# EEG_cap_v1.net
KiCad netlist of a schematic drawn in EAGLE
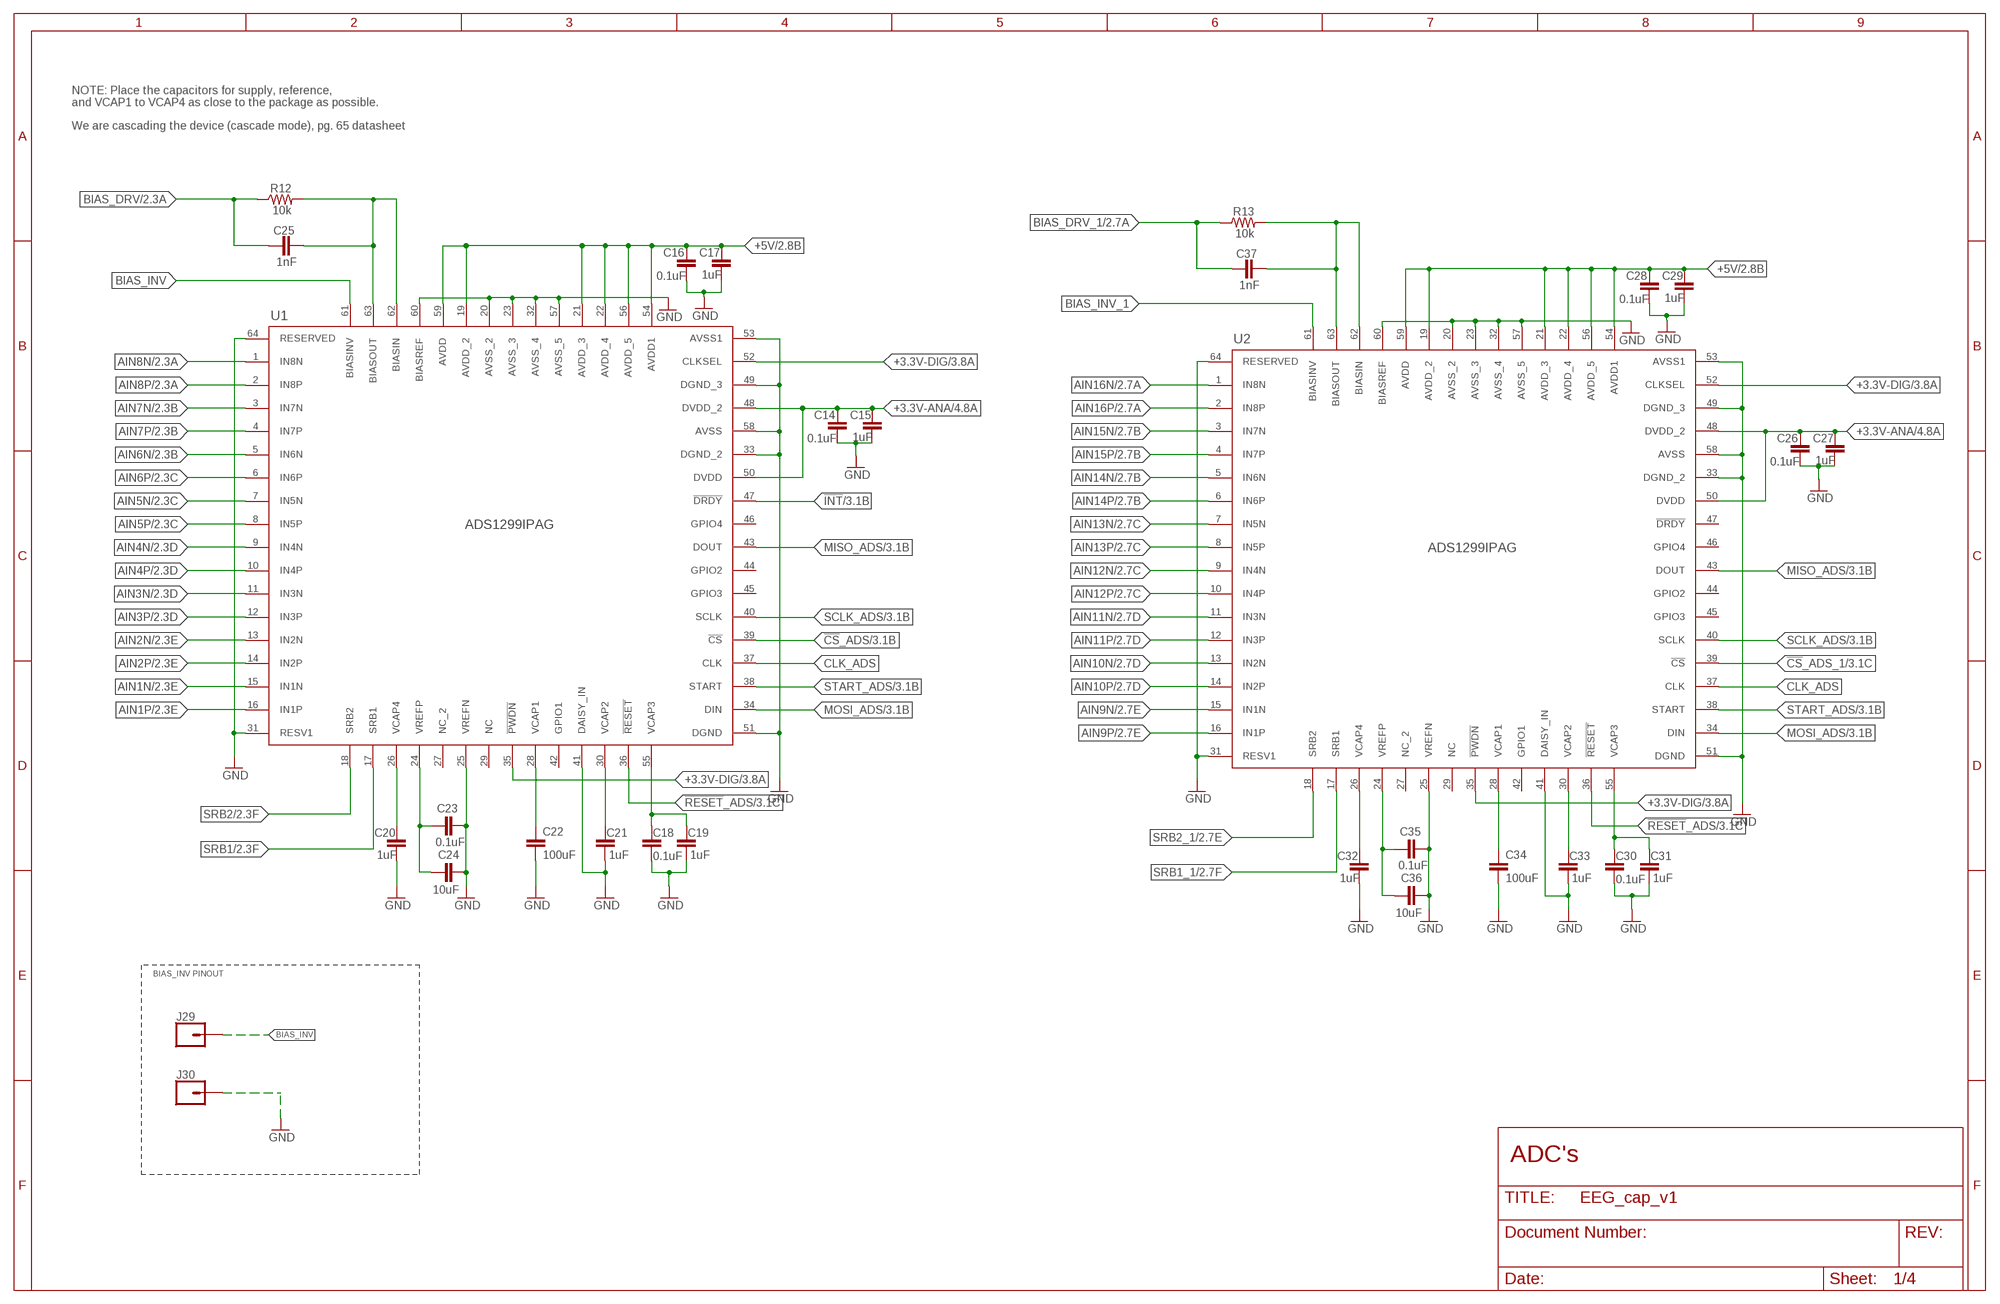
[diagram p0: schematic, sheet 1]
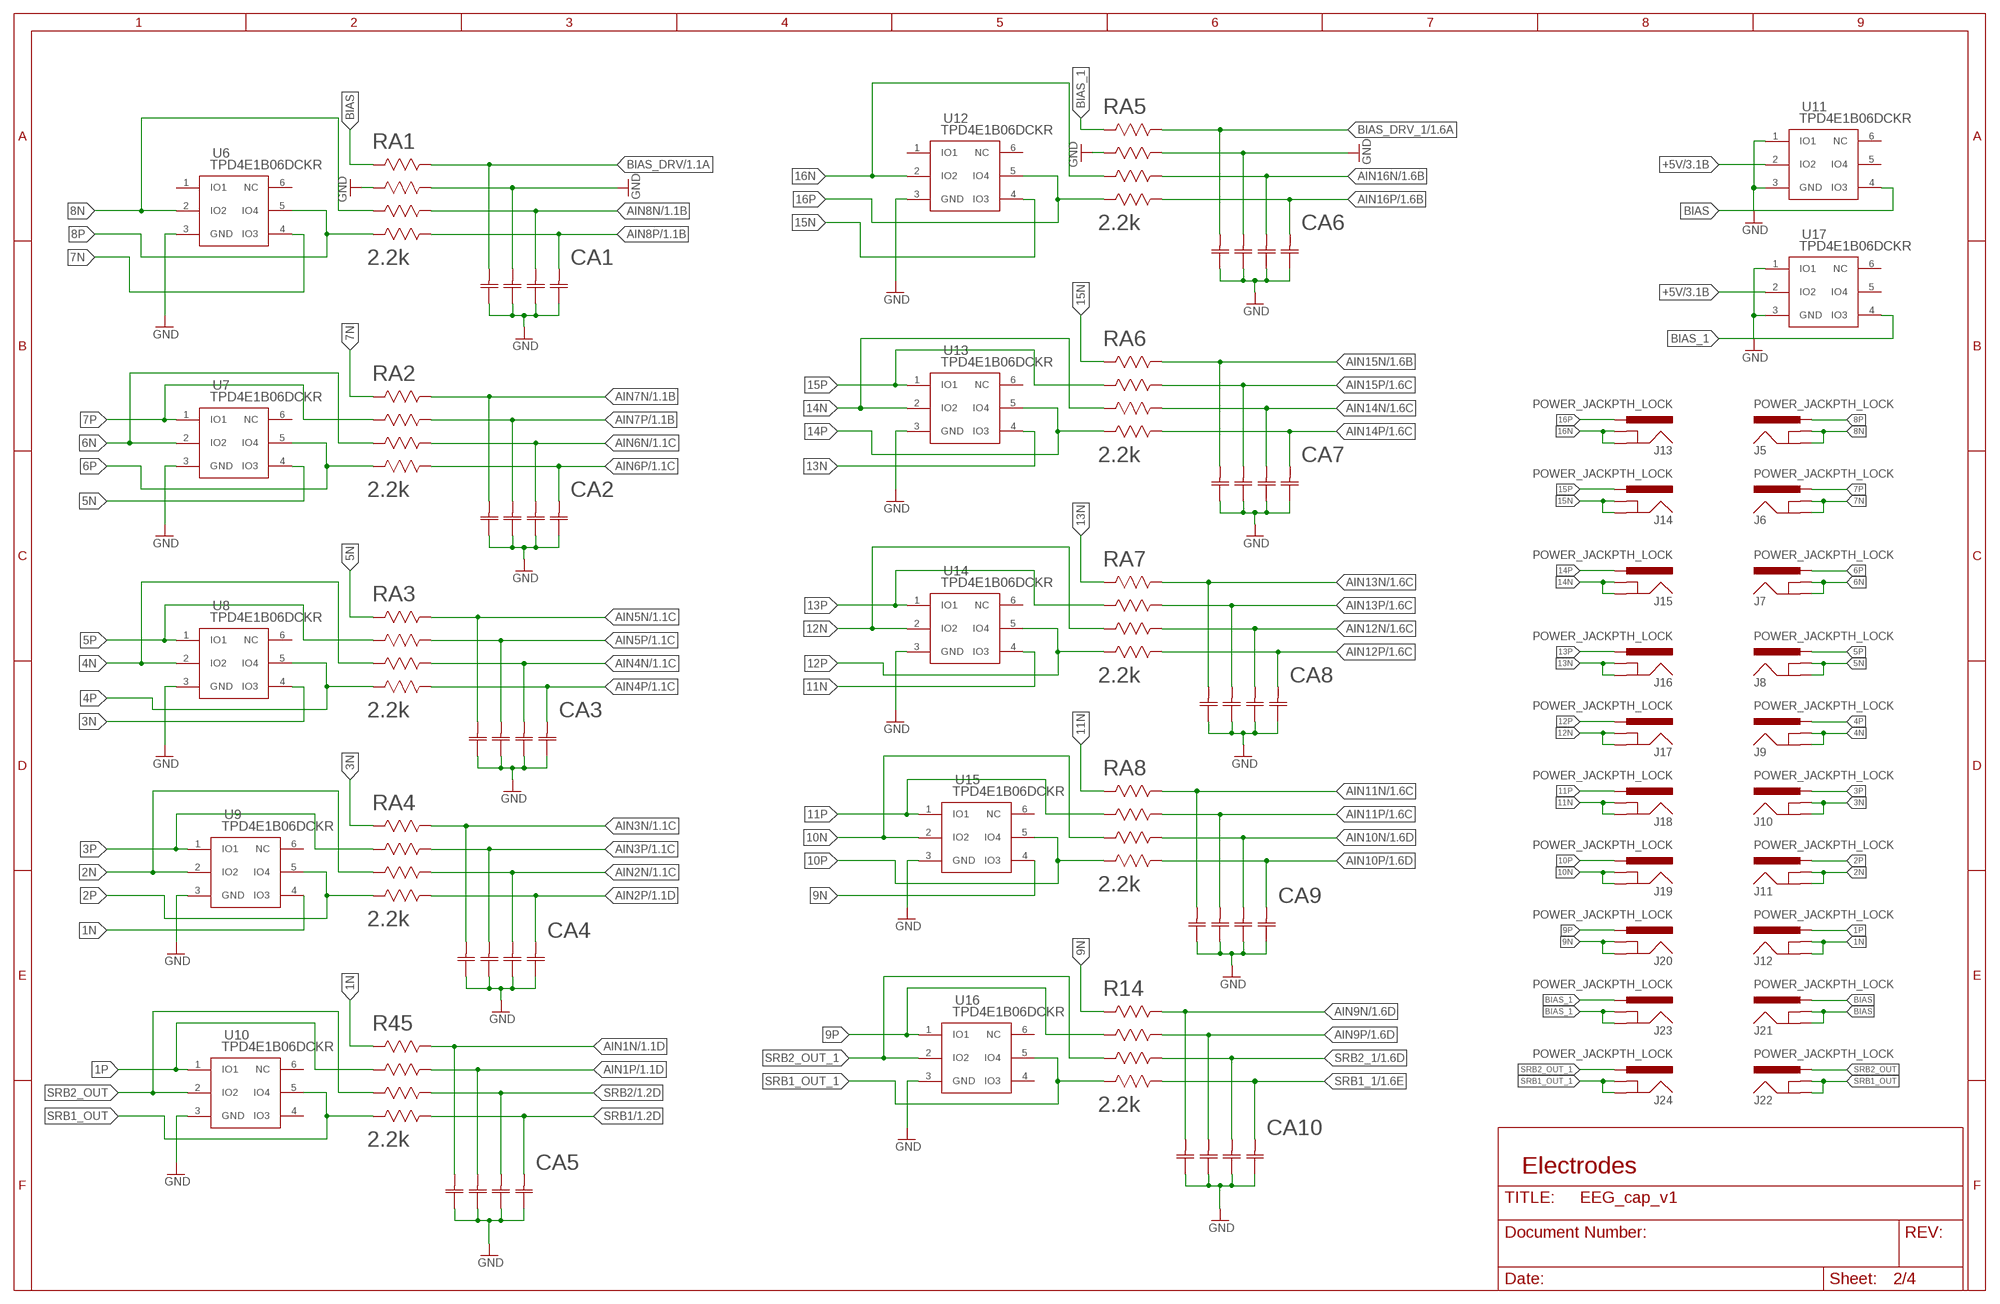
[diagram p1: schematic, sheet 2]
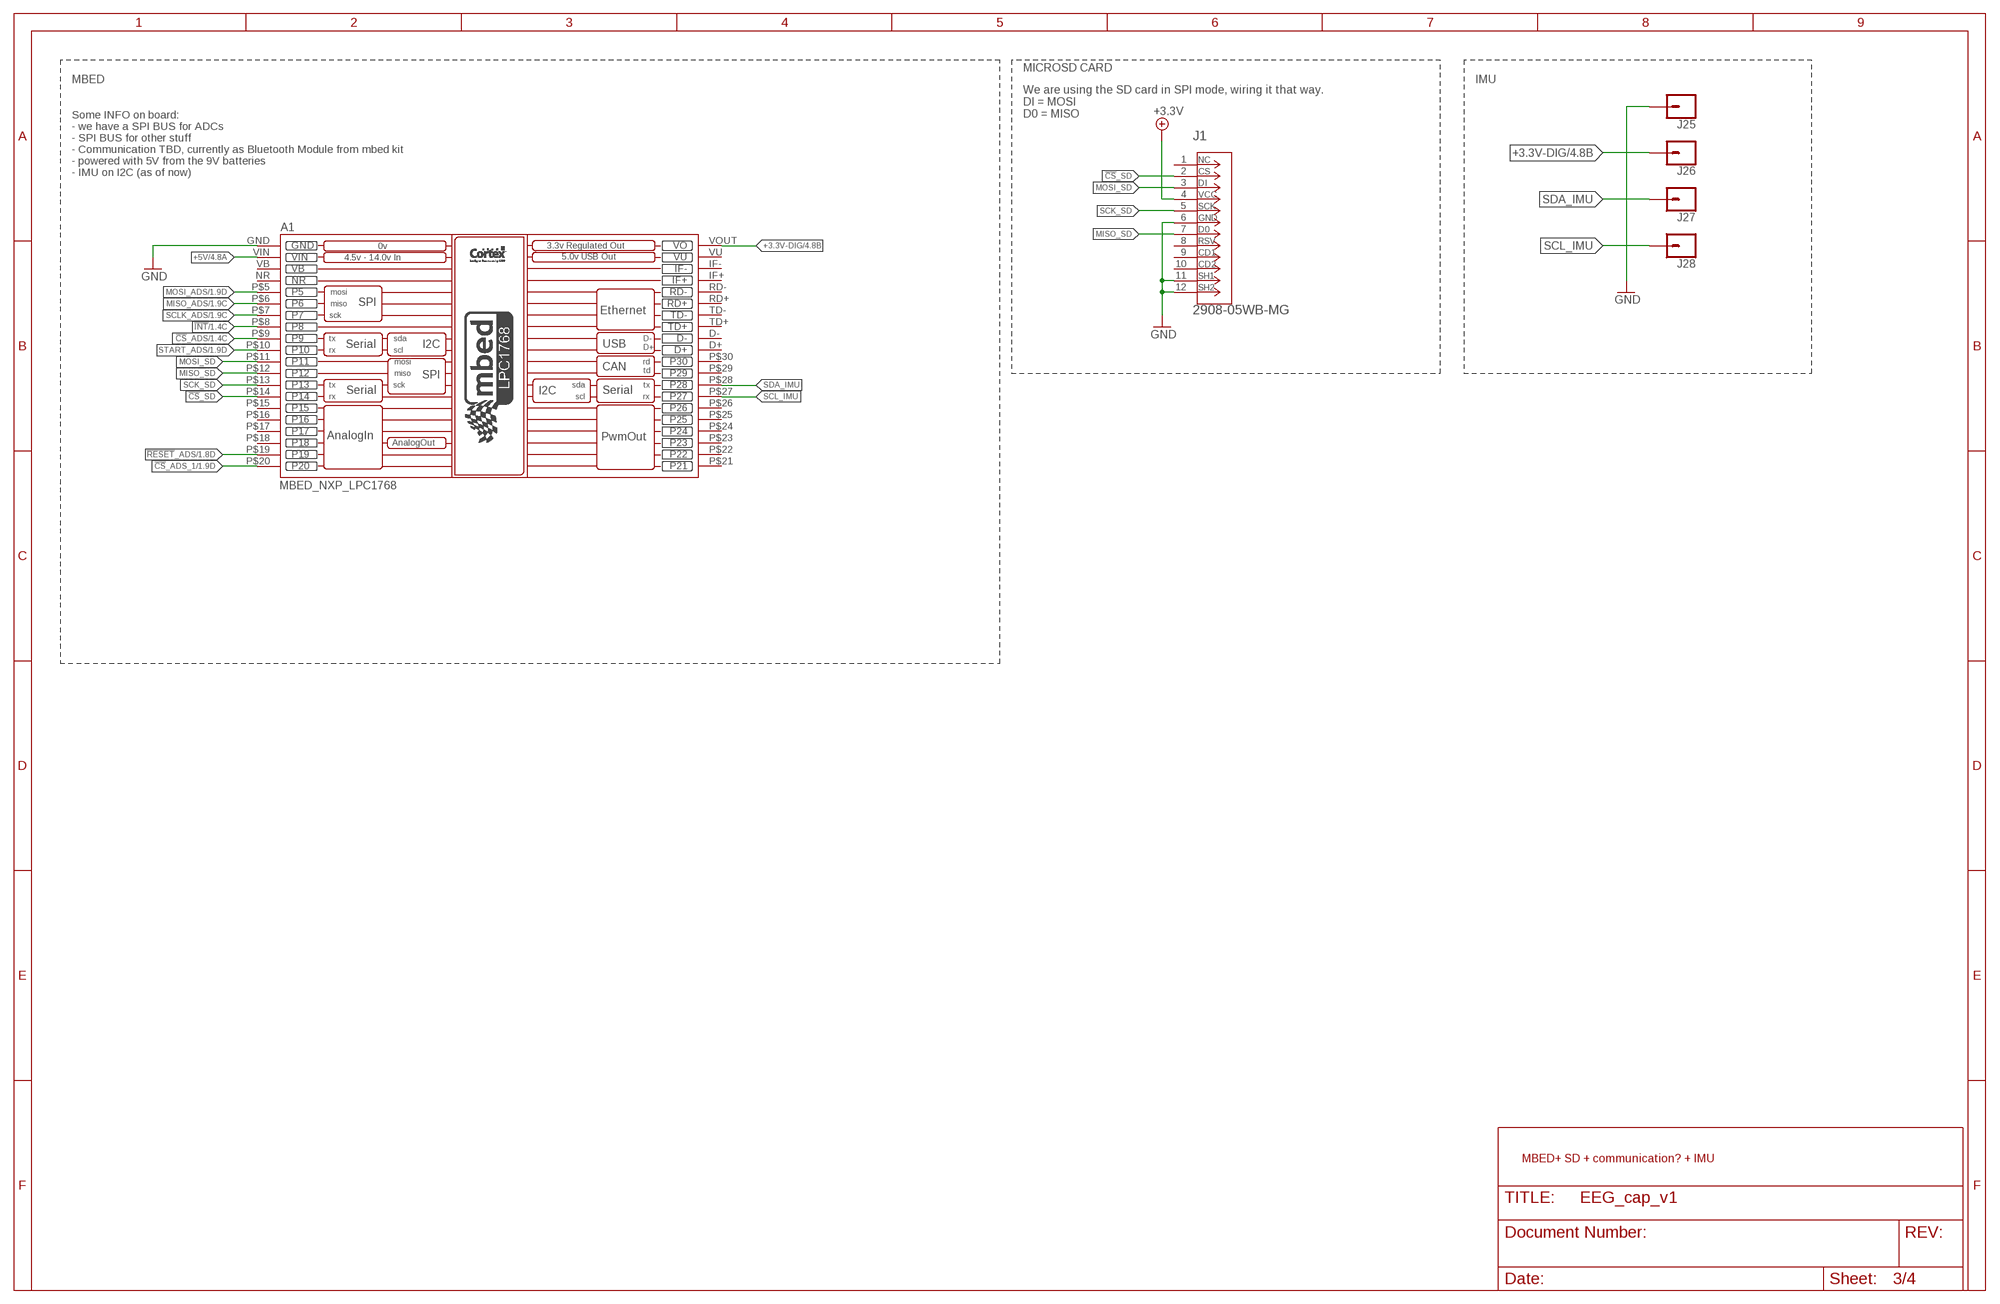
[diagram p2: schematic, sheet 3]
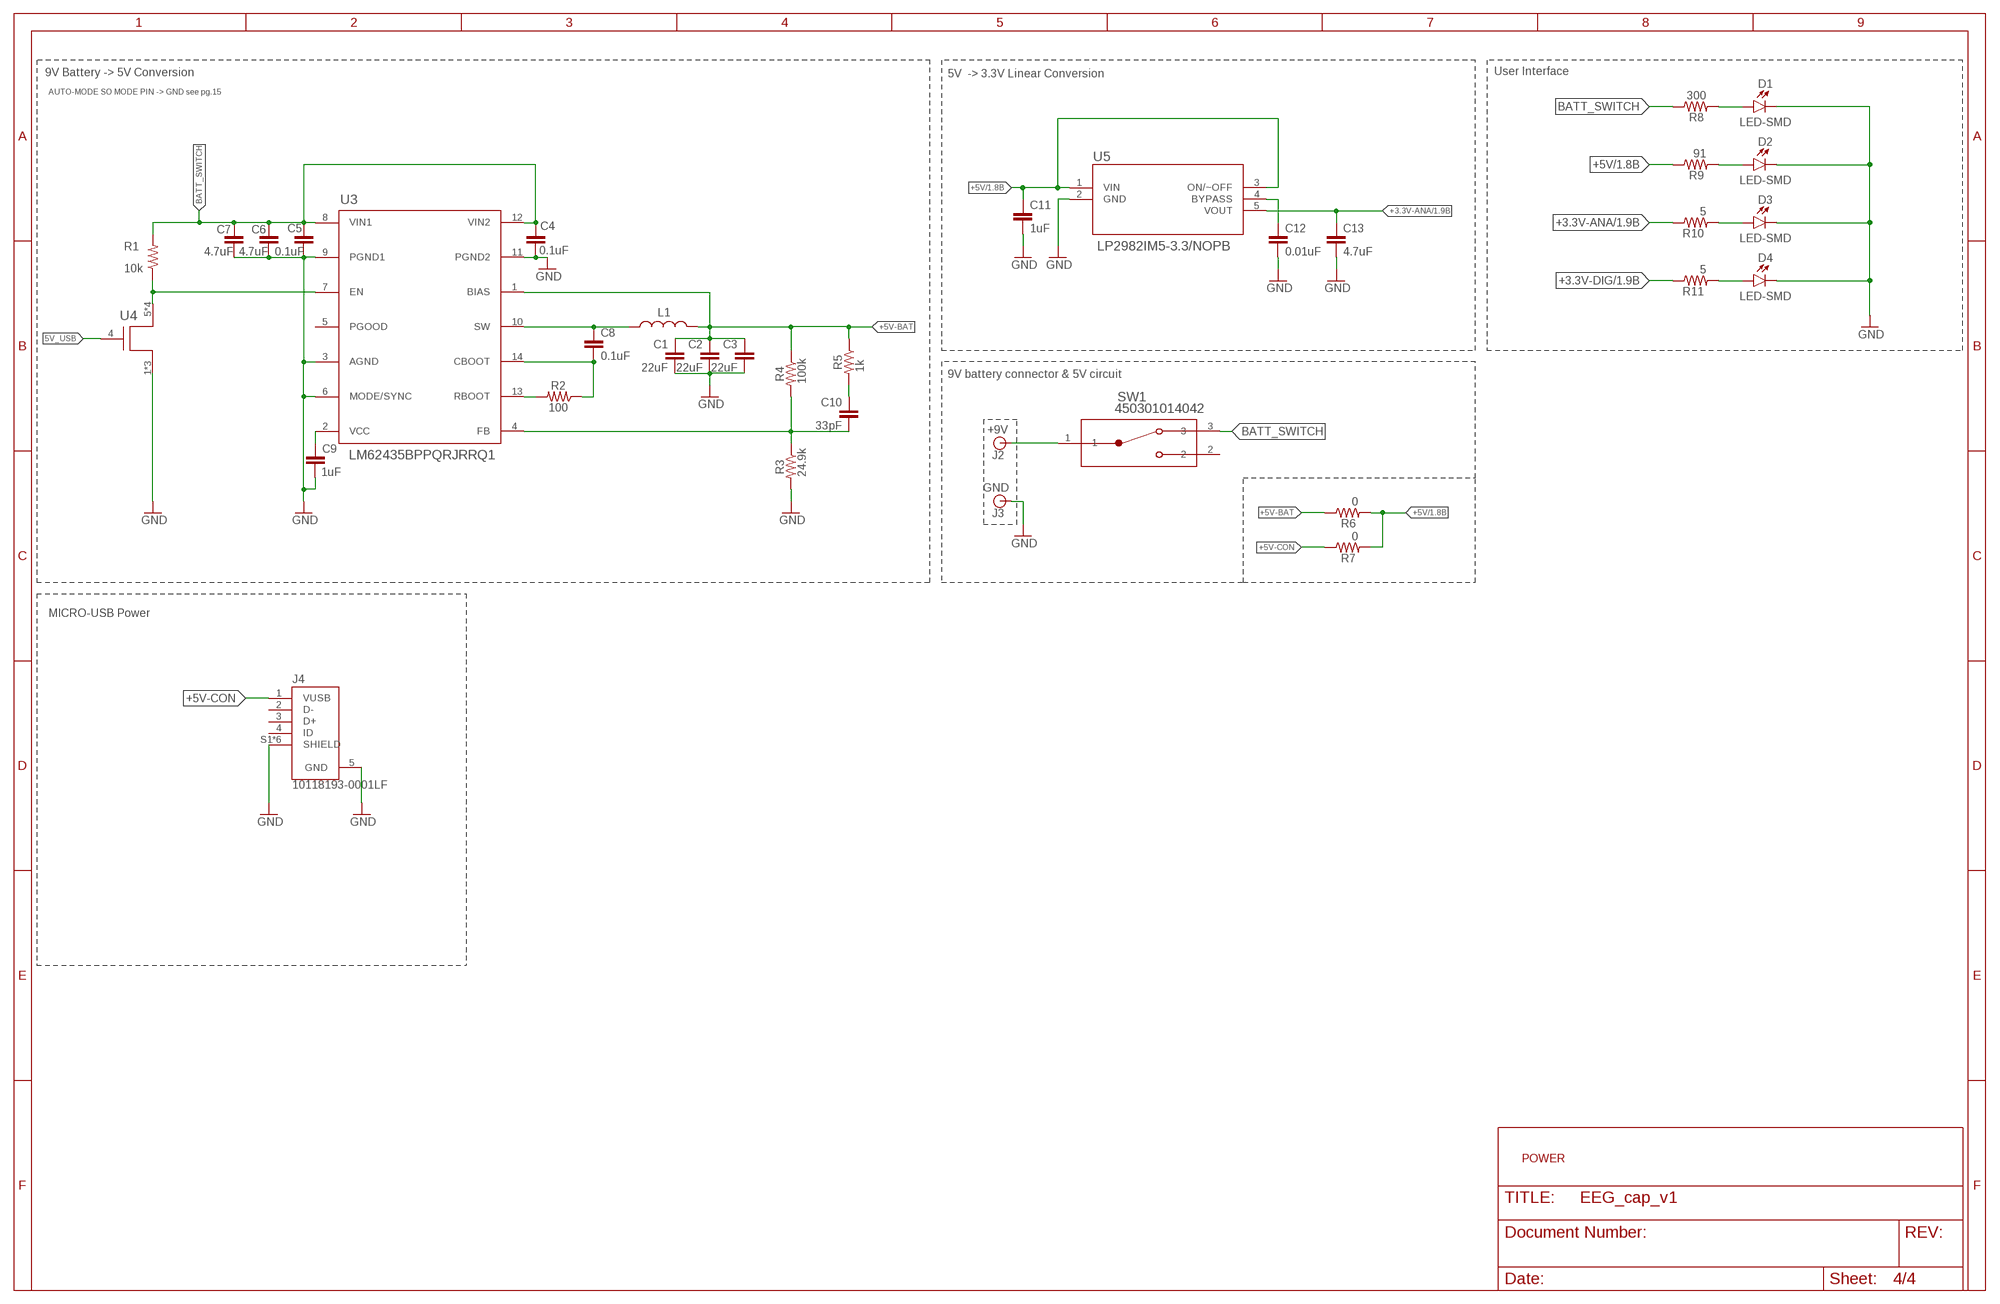
[diagram p3: schematic, sheet 4]

(export (version "E")
  (design (tool "Eeschema 10.0.6"))
  (components
    (comp (ref "A1")
      (value "MBED_NXP_LPC1768")
      (footprint "eagle-import:MBED_LPC1768")
      (libsource (lib "eagle-import") (part "MBED_NXP_LPC1768"))
    )
    (comp (ref "J1")
      (value "2908-05WB-MG")
      (footprint "eagle-import:CONN_3M_2900")
      (fields (field (name "COPYRIGHT") "Copyright (C) 2021 Ultra Librarian. All rights reserved."))
      (libsource (lib "eagle-import") (part "2908-05WB-MG"))
    )
    (comp (ref "J25")
      (value "CONN_01")
      (footprint "eagle-import:1X01")
      (libsource (lib "eagle-import") (part "CONN_01"))
    )
    (comp (ref "J26")
      (value "CONN_01")
      (footprint "eagle-import:1X01")
      (libsource (lib "eagle-import") (part "CONN_01"))
    )
    (comp (ref "J27")
      (value "CONN_01")
      (footprint "eagle-import:1X01")
      (libsource (lib "eagle-import") (part "CONN_01"))
    )
    (comp (ref "J28")
      (value "CONN_01")
      (footprint "eagle-import:1X01")
      (libsource (lib "eagle-import") (part "CONN_01"))
    )
    (comp (ref "CA1")
      (value "CAP_ARRAY")
      (footprint "eagle-import:CAP_CA0612_3P2X1P6_YAG")
      (libsource (lib "eagle-import") (part "CAP_ARRAY"))
    )
    (comp (ref "CA2")
      (value "CAP_ARRAY")
      (footprint "eagle-import:CAP_CA0612_3P2X1P6_YAG")
      (libsource (lib "eagle-import") (part "CAP_ARRAY"))
    )
    (comp (ref "CA3")
      (value "CAP_ARRAY")
      (footprint "eagle-import:CAP_CA0612_3P2X1P6_YAG")
      (libsource (lib "eagle-import") (part "CAP_ARRAY"))
    )
    (comp (ref "CA4")
      (value "CAP_ARRAY")
      (footprint "eagle-import:CAP_CA0612_3P2X1P6_YAG")
      (libsource (lib "eagle-import") (part "CAP_ARRAY"))
    )
    (comp (ref "CA5")
      (value "CAP_ARRAY")
      (footprint "eagle-import:CAP_CA0612_3P2X1P6_YAG")
      (libsource (lib "eagle-import") (part "CAP_ARRAY"))
    )
    (comp (ref "CA6")
      (value "CAP_ARRAY")
      (footprint "eagle-import:CAP_CA0612_3P2X1P6_YAG")
      (libsource (lib "eagle-import") (part "CAP_ARRAY"))
    )
    (comp (ref "CA7")
      (value "CAP_ARRAY")
      (footprint "eagle-import:CAP_CA0612_3P2X1P6_YAG")
      (libsource (lib "eagle-import") (part "CAP_ARRAY"))
    )
    (comp (ref "CA8")
      (value "CAP_ARRAY")
      (footprint "eagle-import:CAP_CA0612_3P2X1P6_YAG")
      (libsource (lib "eagle-import") (part "CAP_ARRAY"))
    )
    (comp (ref "CA9")
      (value "CAP_ARRAY")
      (footprint "eagle-import:CAP_CA0612_3P2X1P6_YAG")
      (libsource (lib "eagle-import") (part "CAP_ARRAY"))
    )
    (comp (ref "CA10")
      (value "CAP_ARRAY")
      (footprint "eagle-import:CAP_CA0612_3P2X1P6_YAG")
      (libsource (lib "eagle-import") (part "CAP_ARRAY"))
    )
    (comp (ref "J5")
      (value "POWER_JACKPTH_LOCK")
      (footprint "eagle-import:POWER_JACK_PTH_LOCK")
      (libsource (lib "eagle-import") (part "POWER_JACKPTH_LOCK"))
    )
    (comp (ref "J6")
      (value "POWER_JACKPTH_LOCK")
      (footprint "eagle-import:POWER_JACK_PTH_LOCK")
      (libsource (lib "eagle-import") (part "POWER_JACKPTH_LOCK"))
    )
    (comp (ref "J7")
      (value "POWER_JACKPTH_LOCK")
      (footprint "eagle-import:POWER_JACK_PTH_LOCK")
      (libsource (lib "eagle-import") (part "POWER_JACKPTH_LOCK"))
    )
    (comp (ref "J8")
      (value "POWER_JACKPTH_LOCK")
      (footprint "eagle-import:POWER_JACK_PTH_LOCK")
      (libsource (lib "eagle-import") (part "POWER_JACKPTH_LOCK"))
    )
    (comp (ref "J9")
      (value "POWER_JACKPTH_LOCK")
      (footprint "eagle-import:POWER_JACK_PTH_LOCK")
      (libsource (lib "eagle-import") (part "POWER_JACKPTH_LOCK"))
    )
    (comp (ref "J10")
      (value "POWER_JACKPTH_LOCK")
      (footprint "eagle-import:POWER_JACK_PTH_LOCK")
      (libsource (lib "eagle-import") (part "POWER_JACKPTH_LOCK"))
    )
    (comp (ref "J11")
      (value "POWER_JACKPTH_LOCK")
      (footprint "eagle-import:POWER_JACK_PTH_LOCK")
      (libsource (lib "eagle-import") (part "POWER_JACKPTH_LOCK"))
    )
    (comp (ref "J12")
      (value "POWER_JACKPTH_LOCK")
      (footprint "eagle-import:POWER_JACK_PTH_LOCK")
      (libsource (lib "eagle-import") (part "POWER_JACKPTH_LOCK"))
    )
    (comp (ref "J13")
      (value "POWER_JACKPTH_LOCK")
      (footprint "eagle-import:POWER_JACK_PTH_LOCK")
      (libsource (lib "eagle-import") (part "POWER_JACKPTH_LOCK"))
    )
    (comp (ref "J14")
      (value "POWER_JACKPTH_LOCK")
      (footprint "eagle-import:POWER_JACK_PTH_LOCK")
      (libsource (lib "eagle-import") (part "POWER_JACKPTH_LOCK"))
    )
    (comp (ref "J15")
      (value "POWER_JACKPTH_LOCK")
      (footprint "eagle-import:POWER_JACK_PTH_LOCK")
      (libsource (lib "eagle-import") (part "POWER_JACKPTH_LOCK"))
    )
    (comp (ref "J16")
      (value "POWER_JACKPTH_LOCK")
      (footprint "eagle-import:POWER_JACK_PTH_LOCK")
      (libsource (lib "eagle-import") (part "POWER_JACKPTH_LOCK"))
    )
    (comp (ref "J17")
      (value "POWER_JACKPTH_LOCK")
      (footprint "eagle-import:POWER_JACK_PTH_LOCK")
      (libsource (lib "eagle-import") (part "POWER_JACKPTH_LOCK"))
    )
    (comp (ref "J18")
      (value "POWER_JACKPTH_LOCK")
      (footprint "eagle-import:POWER_JACK_PTH_LOCK")
      (libsource (lib "eagle-import") (part "POWER_JACKPTH_LOCK"))
    )
    (comp (ref "J19")
      (value "POWER_JACKPTH_LOCK")
      (footprint "eagle-import:POWER_JACK_PTH_LOCK")
      (libsource (lib "eagle-import") (part "POWER_JACKPTH_LOCK"))
    )
    (comp (ref "J20")
      (value "POWER_JACKPTH_LOCK")
      (footprint "eagle-import:POWER_JACK_PTH_LOCK")
      (libsource (lib "eagle-import") (part "POWER_JACKPTH_LOCK"))
    )
    (comp (ref "J21")
      (value "POWER_JACKPTH_LOCK")
      (footprint "eagle-import:POWER_JACK_PTH_LOCK")
      (libsource (lib "eagle-import") (part "POWER_JACKPTH_LOCK"))
    )
    (comp (ref "J22")
      (value "POWER_JACKPTH_LOCK")
      (footprint "eagle-import:POWER_JACK_PTH_LOCK")
      (libsource (lib "eagle-import") (part "POWER_JACKPTH_LOCK"))
    )
    (comp (ref "J23")
      (value "POWER_JACKPTH_LOCK")
      (footprint "eagle-import:POWER_JACK_PTH_LOCK")
      (libsource (lib "eagle-import") (part "POWER_JACKPTH_LOCK"))
    )
    (comp (ref "J24")
      (value "POWER_JACKPTH_LOCK")
      (footprint "eagle-import:POWER_JACK_PTH_LOCK")
      (libsource (lib "eagle-import") (part "POWER_JACKPTH_LOCK"))
    )
    (comp (ref "R14")
      (value "2.2k")
      (footprint "eagle-import:BO_CAT16")
      (fields
        (field (name "MANUFACTURER_PART_NUMBER") "CAT16-220J4LF")
        (field (name "COPYRIGHT") "Copyright (C) 2021 Ultra Librarian. All rights reserved.")
      )
      (libsource (lib "eagle-import") (part "CAT16-220J4LF"))
    )
    (comp (ref "R45")
      (value "2.2k")
      (footprint "eagle-import:BO_CAT16")
      (fields
        (field (name "MANUFACTURER_PART_NUMBER") "CAT16-220J4LF")
        (field (name "COPYRIGHT") "Copyright (C) 2021 Ultra Librarian. All rights reserved.")
      )
      (libsource (lib "eagle-import") (part "CAT16-220J4LF"))
    )
    (comp (ref "RA1")
      (value "2.2k")
      (footprint "eagle-import:BO_CAT16")
      (fields
        (field (name "MANUFACTURER_PART_NUMBER") "CAT16-220J4LF")
        (field (name "COPYRIGHT") "Copyright (C) 2021 Ultra Librarian. All rights reserved.")
      )
      (libsource (lib "eagle-import") (part "CAT16-220J4LF"))
    )
    (comp (ref "RA2")
      (value "2.2k")
      (footprint "eagle-import:BO_CAT16")
      (fields
        (field (name "MANUFACTURER_PART_NUMBER") "CAT16-220J4LF")
        (field (name "COPYRIGHT") "Copyright (C) 2021 Ultra Librarian. All rights reserved.")
      )
      (libsource (lib "eagle-import") (part "CAT16-220J4LF"))
    )
    (comp (ref "RA3")
      (value "2.2k")
      (footprint "eagle-import:BO_CAT16")
      (fields
        (field (name "MANUFACTURER_PART_NUMBER") "CAT16-220J4LF")
        (field (name "COPYRIGHT") "Copyright (C) 2021 Ultra Librarian. All rights reserved.")
      )
      (libsource (lib "eagle-import") (part "CAT16-220J4LF"))
    )
    (comp (ref "RA4")
      (value "2.2k")
      (footprint "eagle-import:BO_CAT16")
      (fields
        (field (name "MANUFACTURER_PART_NUMBER") "CAT16-220J4LF")
        (field (name "COPYRIGHT") "Copyright (C) 2021 Ultra Librarian. All rights reserved.")
      )
      (libsource (lib "eagle-import") (part "CAT16-220J4LF"))
    )
    (comp (ref "RA5")
      (value "2.2k")
      (footprint "eagle-import:BO_CAT16")
      (fields
        (field (name "MANUFACTURER_PART_NUMBER") "CAT16-220J4LF")
        (field (name "COPYRIGHT") "Copyright (C) 2021 Ultra Librarian. All rights reserved.")
      )
      (libsource (lib "eagle-import") (part "CAT16-220J4LF"))
    )
    (comp (ref "RA6")
      (value "2.2k")
      (footprint "eagle-import:BO_CAT16")
      (fields
        (field (name "MANUFACTURER_PART_NUMBER") "CAT16-220J4LF")
        (field (name "COPYRIGHT") "Copyright (C) 2021 Ultra Librarian. All rights reserved.")
      )
      (libsource (lib "eagle-import") (part "CAT16-220J4LF"))
    )
    (comp (ref "RA7")
      (value "2.2k")
      (footprint "eagle-import:BO_CAT16")
      (fields
        (field (name "MANUFACTURER_PART_NUMBER") "CAT16-220J4LF")
        (field (name "COPYRIGHT") "Copyright (C) 2021 Ultra Librarian. All rights reserved.")
      )
      (libsource (lib "eagle-import") (part "CAT16-220J4LF"))
    )
    (comp (ref "RA8")
      (value "2.2k")
      (footprint "eagle-import:BO_CAT16")
      (fields
        (field (name "MANUFACTURER_PART_NUMBER") "CAT16-220J4LF")
        (field (name "COPYRIGHT") "Copyright (C) 2021 Ultra Librarian. All rights reserved.")
      )
      (libsource (lib "eagle-import") (part "CAT16-220J4LF"))
    )
    (comp (ref "U6")
      (value "TPD4E1B06DCKR")
      (footprint "eagle-import:DCK6_TEX")
      (fields (field (name "COPYRIGHT") "Copyright (C) 2021 Ultra Librarian. All rights reserved."))
      (libsource (lib "eagle-import") (part "TPD4E1B06DCKR"))
    )
    (comp (ref "U7")
      (value "TPD4E1B06DCKR")
      (footprint "eagle-import:DCK6_TEX")
      (fields (field (name "COPYRIGHT") "Copyright (C) 2021 Ultra Librarian. All rights reserved."))
      (libsource (lib "eagle-import") (part "TPD4E1B06DCKR"))
    )
    (comp (ref "U8")
      (value "TPD4E1B06DCKR")
      (footprint "eagle-import:DCK6_TEX")
      (fields (field (name "COPYRIGHT") "Copyright (C) 2021 Ultra Librarian. All rights reserved."))
      (libsource (lib "eagle-import") (part "TPD4E1B06DCKR"))
    )
    (comp (ref "U9")
      (value "TPD4E1B06DCKR")
      (footprint "eagle-import:DCK6_TEX")
      (fields (field (name "COPYRIGHT") "Copyright (C) 2021 Ultra Librarian. All rights reserved."))
      (libsource (lib "eagle-import") (part "TPD4E1B06DCKR"))
    )
    (comp (ref "U10")
      (value "TPD4E1B06DCKR")
      (footprint "eagle-import:DCK6_TEX")
      (fields (field (name "COPYRIGHT") "Copyright (C) 2021 Ultra Librarian. All rights reserved."))
      (libsource (lib "eagle-import") (part "TPD4E1B06DCKR"))
    )
    (comp (ref "U11")
      (value "TPD4E1B06DCKR")
      (footprint "eagle-import:DCK6_TEX")
      (fields (field (name "COPYRIGHT") "Copyright (C) 2021 Ultra Librarian. All rights reserved."))
      (libsource (lib "eagle-import") (part "TPD4E1B06DCKR"))
    )
    (comp (ref "U12")
      (value "TPD4E1B06DCKR")
      (footprint "eagle-import:DCK6_TEX")
      (fields (field (name "COPYRIGHT") "Copyright (C) 2021 Ultra Librarian. All rights reserved."))
      (libsource (lib "eagle-import") (part "TPD4E1B06DCKR"))
    )
    (comp (ref "U13")
      (value "TPD4E1B06DCKR")
      (footprint "eagle-import:DCK6_TEX")
      (fields (field (name "COPYRIGHT") "Copyright (C) 2021 Ultra Librarian. All rights reserved."))
      (libsource (lib "eagle-import") (part "TPD4E1B06DCKR"))
    )
    (comp (ref "U14")
      (value "TPD4E1B06DCKR")
      (footprint "eagle-import:DCK6_TEX")
      (fields (field (name "COPYRIGHT") "Copyright (C) 2021 Ultra Librarian. All rights reserved."))
      (libsource (lib "eagle-import") (part "TPD4E1B06DCKR"))
    )
    (comp (ref "U15")
      (value "TPD4E1B06DCKR")
      (footprint "eagle-import:DCK6_TEX")
      (fields (field (name "COPYRIGHT") "Copyright (C) 2021 Ultra Librarian. All rights reserved."))
      (libsource (lib "eagle-import") (part "TPD4E1B06DCKR"))
    )
    (comp (ref "U16")
      (value "TPD4E1B06DCKR")
      (footprint "eagle-import:DCK6_TEX")
      (fields (field (name "COPYRIGHT") "Copyright (C) 2021 Ultra Librarian. All rights reserved."))
      (libsource (lib "eagle-import") (part "TPD4E1B06DCKR"))
    )
    (comp (ref "U17")
      (value "TPD4E1B06DCKR")
      (footprint "eagle-import:DCK6_TEX")
      (fields (field (name "COPYRIGHT") "Copyright (C) 2021 Ultra Librarian. All rights reserved."))
      (libsource (lib "eagle-import") (part "TPD4E1B06DCKR"))
    )
    (comp (ref "C14")
      (value "0.1uF")
      (footprint "eagle-import:C0603")
      (libsource (lib "eagle-import") (part "C-EUC0603"))
    )
    (comp (ref "C15")
      (value "1uF")
      (footprint "eagle-import:C0603")
      (libsource (lib "eagle-import") (part "C-EUC0603"))
    )
    (comp (ref "C16")
      (value "0.1uF")
      (footprint "eagle-import:C0603")
      (libsource (lib "eagle-import") (part "C-EUC0603"))
    )
    (comp (ref "C17")
      (value "1uF")
      (footprint "eagle-import:C0603")
      (libsource (lib "eagle-import") (part "C-EUC0603"))
    )
    (comp (ref "C18")
      (value "0.1uF")
      (footprint "eagle-import:C0603")
      (libsource (lib "eagle-import") (part "C-EUC0603"))
    )
    (comp (ref "C19")
      (value "1uF")
      (footprint "eagle-import:C0603")
      (libsource (lib "eagle-import") (part "C-EUC0603"))
    )
    (comp (ref "C20")
      (value "1uF")
      (footprint "eagle-import:C0603")
      (libsource (lib "eagle-import") (part "C-EUC0603"))
    )
    (comp (ref "C21")
      (value "1uF")
      (footprint "eagle-import:C0603")
      (libsource (lib "eagle-import") (part "C-EUC0603"))
    )
    (comp (ref "C22")
      (value "100uF")
      (footprint "eagle-import:C1210")
      (libsource (lib "eagle-import") (part "C-EUC1210"))
    )
    (comp (ref "C23")
      (value "0.1uF")
      (footprint "eagle-import:C0603")
      (libsource (lib "eagle-import") (part "C-EUC0603"))
    )
    (comp (ref "C24")
      (value "10uF")
      (footprint "eagle-import:C0805")
      (libsource (lib "eagle-import") (part "C-EUC0805"))
    )
    (comp (ref "C25")
      (value "1nF")
      (footprint "eagle-import:C0603")
      (libsource (lib "eagle-import") (part "C-EUC0603"))
    )
    (comp (ref "C26")
      (value "0.1uF")
      (footprint "eagle-import:C0603")
      (libsource (lib "eagle-import") (part "C-EUC0603"))
    )
    (comp (ref "C27")
      (value "1uF")
      (footprint "eagle-import:C0603")
      (libsource (lib "eagle-import") (part "C-EUC0603"))
    )
    (comp (ref "C28")
      (value "0.1uF")
      (footprint "eagle-import:C0603")
      (libsource (lib "eagle-import") (part "C-EUC0603"))
    )
    (comp (ref "C29")
      (value "1uF")
      (footprint "eagle-import:C0603")
      (libsource (lib "eagle-import") (part "C-EUC0603"))
    )
    (comp (ref "C30")
      (value "0.1uF")
      (footprint "eagle-import:C0603")
      (libsource (lib "eagle-import") (part "C-EUC0603"))
    )
    (comp (ref "C31")
      (value "1uF")
      (footprint "eagle-import:C0603")
      (libsource (lib "eagle-import") (part "C-EUC0603"))
    )
    (comp (ref "C32")
      (value "1uF")
      (footprint "eagle-import:C0603")
      (libsource (lib "eagle-import") (part "C-EUC0603"))
    )
    (comp (ref "C33")
      (value "1uF")
      (footprint "eagle-import:C0603")
      (libsource (lib "eagle-import") (part "C-EUC0603"))
    )
    (comp (ref "C34")
      (value "100uF")
      (footprint "eagle-import:C1210")
      (libsource (lib "eagle-import") (part "C-EUC1210"))
    )
    (comp (ref "C35")
      (value "0.1uF")
      (footprint "eagle-import:C0603")
      (libsource (lib "eagle-import") (part "C-EUC0603"))
    )
    (comp (ref "C36")
      (value "10uF")
      (footprint "eagle-import:C0805")
      (libsource (lib "eagle-import") (part "C-EUC0805"))
    )
    (comp (ref "C37")
      (value "1nF")
      (footprint "eagle-import:C0603")
      (libsource (lib "eagle-import") (part "C-EUC0603"))
    )
    (comp (ref "J29")
      (value "CONN_01")
      (footprint "eagle-import:1X01")
      (libsource (lib "eagle-import") (part "CONN_01"))
    )
    (comp (ref "J30")
      (value "CONN_01")
      (footprint "eagle-import:1X01")
      (libsource (lib "eagle-import") (part "CONN_01"))
    )
    (comp (ref "R12")
      (value "10k")
      (footprint "eagle-import:R0805")
      (libsource (lib "eagle-import") (part "R-US_R0805"))
    )
    (comp (ref "R13")
      (value "10k")
      (footprint "eagle-import:R0805")
      (libsource (lib "eagle-import") (part "R-US_R0805"))
    )
    (comp (ref "U1")
      (value "ADS1299IPAG")
      (footprint "eagle-import:PAG64_TEX")
      (fields (field (name "COPYRIGHT") "Copyright (C) 2021 Ultra Librarian. All rights reserved."))
      (libsource (lib "eagle-import") (part "ADS1299IPAG"))
    )
    (comp (ref "U2")
      (value "ADS1299IPAG")
      (footprint "eagle-import:PAG64_TEX")
      (fields (field (name "COPYRIGHT") "Copyright (C) 2021 Ultra Librarian. All rights reserved."))
      (libsource (lib "eagle-import") (part "ADS1299IPAG"))
    )
    (comp (ref "C1")
      (value "22uF")
      (footprint "eagle-import:C0805")
      (libsource (lib "eagle-import") (part "C-EUC0805"))
    )
    (comp (ref "C2")
      (value "22uF")
      (footprint "eagle-import:C0805")
      (libsource (lib "eagle-import") (part "C-EUC0805"))
    )
    (comp (ref "C3")
      (value "22uF")
      (footprint "eagle-import:C0805")
      (libsource (lib "eagle-import") (part "C-EUC0805"))
    )
    (comp (ref "C4")
      (value "0.1uF")
      (footprint "eagle-import:C0805")
      (libsource (lib "eagle-import") (part "C-EUC0805"))
    )
    (comp (ref "C5")
      (value "0.1uF")
      (footprint "eagle-import:C0805")
      (libsource (lib "eagle-import") (part "C-EUC0805"))
    )
    (comp (ref "C6")
      (value "4.7uF")
      (footprint "eagle-import:C0805")
      (libsource (lib "eagle-import") (part "C-EUC0805"))
    )
    (comp (ref "C7")
      (value "4.7uF")
      (footprint "eagle-import:C0805")
      (libsource (lib "eagle-import") (part "C-EUC0805"))
    )
    (comp (ref "C8")
      (value "0.1uF")
      (footprint "eagle-import:C0805")
      (libsource (lib "eagle-import") (part "C-EUC0805"))
    )
    (comp (ref "C9")
      (value "1uF")
      (footprint "eagle-import:C0805")
      (libsource (lib "eagle-import") (part "C-EUC0805"))
    )
    (comp (ref "C10")
      (value "33pF")
      (footprint "eagle-import:C0805")
      (libsource (lib "eagle-import") (part "C-EUC0805"))
    )
    (comp (ref "C11")
      (value "1uF")
      (footprint "eagle-import:C0805")
      (libsource (lib "eagle-import") (part "C-EUC0805"))
    )
    (comp (ref "C12")
      (value "0.01uF")
      (footprint "eagle-import:C0805")
      (libsource (lib "eagle-import") (part "C-EUC0805"))
    )
    (comp (ref "C13")
      (value "4.7uF")
      (footprint "eagle-import:C0805")
      (libsource (lib "eagle-import") (part "C-EUC0805"))
    )
    (comp (ref "D1")
      (value "LED-SMD")
      (footprint "eagle-import:LED0603")
      (libsource (lib "eagle-import") (part "LED-SMD"))
    )
    (comp (ref "D2")
      (value "LED-SMD")
      (footprint "eagle-import:LED0603")
      (libsource (lib "eagle-import") (part "LED-SMD"))
    )
    (comp (ref "D3")
      (value "LED-SMD")
      (footprint "eagle-import:LED0603")
      (libsource (lib "eagle-import") (part "LED-SMD"))
    )
    (comp (ref "D4")
      (value "LED-SMD")
      (footprint "eagle-import:LED0603")
      (libsource (lib "eagle-import") (part "LED-SMD"))
    )
    (comp (ref "J2")
      (value "+9V")
      (footprint "eagle-import:BANANA_CONN")
      (libsource (lib "eagle-import") (part "BANANA_CONN"))
    )
    (comp (ref "J3")
      (value "GND")
      (footprint "eagle-import:BANANA_CONN")
      (libsource (lib "eagle-import") (part "BANANA_CONN"))
    )
    (comp (ref "J4")
      (value "10118193-0001LF")
      (footprint "eagle-import:FCI_10118193-0001LF")
      (libsource (lib "eagle-import") (part "10118193-0001LF"))
    )
    (comp (ref "L1")
      (value "DFE252010P-1R5M=P2")
      (footprint "eagle-import:INDC2520X100N")
      (fields (field (name "DIGI-KEY_PART_NUMBER") "490-10636-1-ND") (field (name "MF") "Murata"))
      (libsource (lib "eagle-import") (part "DFE252010P-1R5M=P2"))
    )
    (comp (ref "R1")
      (value "10k")
      (footprint "eagle-import:R0805")
      (libsource (lib "eagle-import") (part "R-US_R0805"))
    )
    (comp (ref "R2")
      (value "100")
      (footprint "eagle-import:R0805")
      (libsource (lib "eagle-import") (part "R-US_R0805"))
    )
    (comp (ref "R3")
      (value "24.9k")
      (footprint "eagle-import:R0805")
      (libsource (lib "eagle-import") (part "R-US_R0805"))
    )
    (comp (ref "R4")
      (value "100k")
      (footprint "eagle-import:R0805")
      (libsource (lib "eagle-import") (part "R-US_R0805"))
    )
    (comp (ref "R5")
      (value "1k")
      (footprint "eagle-import:R0805")
      (libsource (lib "eagle-import") (part "R-US_R0805"))
    )
    (comp (ref "R6")
      (value "0")
      (footprint "eagle-import:R0805")
      (libsource (lib "eagle-import") (part "R-US_R0805"))
    )
    (comp (ref "R7")
      (value "0")
      (footprint "eagle-import:R0805")
      (libsource (lib "eagle-import") (part "R-US_R0805"))
    )
    (comp (ref "R8")
      (value "300")
      (footprint "eagle-import:R0805")
      (libsource (lib "eagle-import") (part "R-US_R0805"))
    )
    (comp (ref "R9")
      (value "91")
      (footprint "eagle-import:R0805")
      (libsource (lib "eagle-import") (part "R-US_R0805"))
    )
    (comp (ref "R10")
      (value "5")
      (footprint "eagle-import:R0805")
      (libsource (lib "eagle-import") (part "R-US_R0805"))
    )
    (comp (ref "R11")
      (value "5")
      (footprint "eagle-import:R0805")
      (libsource (lib "eagle-import") (part "R-US_R0805"))
    )
    (comp (ref "SW1")
      (value "450301014042")
      (footprint "eagle-import:SW_450301014042_WRE")
      (fields (field (name "COPYRIGHT") "Copyright (C) 2021 Ultra Librarian. All rights reserved."))
      (libsource (lib "eagle-import") (part "450301014042"))
    )
    (comp (ref "U3")
      (value "LM62435BPPQRJRRQ1")
      (footprint "eagle-import:VQFN-HR14_RJR_TEX")
      (fields (field (name "COPYRIGHT") "Copyright (C) 2021 Ultra Librarian. All rights reserved."))
      (libsource (lib "eagle-import") (part "LM62435BPPQRJRRQ1"))
    )
    (comp (ref "U4")
      (value "CSD17579Q5AT")
      (footprint "eagle-import:DQJ8_TEX")
      (fields (field (name "COPYRIGHT") "Copyright (C) 2021 Ultra Librarian. All rights reserved."))
      (libsource (lib "eagle-import") (part "CSD17579Q5AT"))
    )
    (comp (ref "U5")
      (value "LP2982IM5-3.3/NOPB")
      (footprint "eagle-import:MF05A")
      (fields (field (name "COPYRIGHT") "Copyright (C) 2021 Ultra Librarian. All rights reserved."))
      (libsource (lib "eagle-import") (part "LP2982IM5-3.3/NOPB"))
    )
  )
  (nets
    (net (code "1") (name "+3.3V") (class "Default")
      (node (ref "J1") (pin "4") (pinfunction "4_4") (pintype "passive"))
    )
    (net (code "2") (name "+3.3V-ANA") (class "Default")
      (node (ref "C13") (pin "1") (pinfunction "1_1") (pintype "passive"))
      (node (ref "C14") (pin "1") (pinfunction "1_1") (pintype "passive"))
      (node (ref "C15") (pin "1") (pinfunction "1_1") (pintype "passive"))
      (node (ref "C26") (pin "1") (pinfunction "1_1") (pintype "passive"))
      (node (ref "C27") (pin "1") (pinfunction "1_1") (pintype "passive"))
      (node (ref "R10") (pin "1") (pinfunction "1_1") (pintype "passive"))
      (node (ref "U1") (pin "48") (pinfunction "DVDD_2_48") (pintype "power_in"))
      (node (ref "U1") (pin "50") (pinfunction "DVDD_50") (pintype "power_in"))
      (node (ref "U2") (pin "48") (pinfunction "DVDD_2_48") (pintype "power_in"))
      (node (ref "U2") (pin "50") (pinfunction "DVDD_50") (pintype "power_in"))
      (node (ref "U5") (pin "5") (pinfunction "VOUT_5") (pintype "output"))
    )
    (net (code "3") (name "+3.3V-DIG") (class "Default")
      (node (ref "A1") (pin "VOUT") (pinfunction "VO_VOUT") (pintype "passive"))
      (node (ref "J26") (pin "1") (pinfunction "1_1") (pintype "passive"))
      (node (ref "R11") (pin "1") (pinfunction "1_1") (pintype "passive"))
      (node (ref "U1") (pin "35") (pinfunction "~{PWDN}_35") (pintype "power_in"))
      (node (ref "U1") (pin "52") (pinfunction "CLKSEL_52") (pintype "input"))
      (node (ref "U2") (pin "35") (pinfunction "~{PWDN}_35") (pintype "power_in"))
      (node (ref "U2") (pin "52") (pinfunction "CLKSEL_52") (pintype "input"))
    )
    (net (code "4") (name "+5V") (class "Default")
      (node (ref "A1") (pin "VIN") (pinfunction "VIN_VIN") (pintype "passive"))
      (node (ref "C11") (pin "1") (pinfunction "1_1") (pintype "passive"))
      (node (ref "C16") (pin "1") (pinfunction "1_1") (pintype "passive"))
      (node (ref "C17") (pin "1") (pinfunction "1_1") (pintype "passive"))
      (node (ref "C28") (pin "1") (pinfunction "1_1") (pintype "passive"))
      (node (ref "C29") (pin "1") (pinfunction "1_1") (pintype "passive"))
      (node (ref "R6") (pin "2") (pinfunction "2_2") (pintype "passive"))
      (node (ref "R7") (pin "2") (pinfunction "2_2") (pintype "passive"))
      (node (ref "R9") (pin "1") (pinfunction "1_1") (pintype "passive"))
      (node (ref "U1") (pin "19") (pinfunction "AVDD_2_19") (pintype "power_in"))
      (node (ref "U1") (pin "21") (pinfunction "AVDD_3_21") (pintype "power_in"))
      (node (ref "U1") (pin "22") (pinfunction "AVDD_4_22") (pintype "power_in"))
      (node (ref "U1") (pin "54") (pinfunction "AVDD1_54") (pintype "power_in"))
      (node (ref "U1") (pin "56") (pinfunction "AVDD_5_56") (pintype "power_in"))
      (node (ref "U1") (pin "59") (pinfunction "AVDD_59") (pintype "power_in"))
      (node (ref "U11") (pin "2") (pinfunction "IO2_2") (pintype "bidirectional"))
      (node (ref "U17") (pin "2") (pinfunction "IO2_2") (pintype "bidirectional"))
      (node (ref "U2") (pin "19") (pinfunction "AVDD_2_19") (pintype "power_in"))
      (node (ref "U2") (pin "21") (pinfunction "AVDD_3_21") (pintype "power_in"))
      (node (ref "U2") (pin "22") (pinfunction "AVDD_4_22") (pintype "power_in"))
      (node (ref "U2") (pin "54") (pinfunction "AVDD1_54") (pintype "power_in"))
      (node (ref "U2") (pin "56") (pinfunction "AVDD_5_56") (pintype "power_in"))
      (node (ref "U2") (pin "59") (pinfunction "AVDD_59") (pintype "power_in"))
      (node (ref "U5") (pin "1") (pinfunction "VIN_1") (pintype "input"))
      (node (ref "U5") (pin "3") (pinfunction "ON/~{OFF}_3") (pintype "passive"))
    )
    (net (code "5") (name "+5V-BAT") (class "Default")
      (node (ref "C1") (pin "1") (pinfunction "1_1") (pintype "passive"))
      (node (ref "C2") (pin "1") (pinfunction "1_1") (pintype "passive"))
      (node (ref "C3") (pin "1") (pinfunction "1_1") (pintype "passive"))
      (node (ref "L1") (pin "2") (pinfunction "2_2") (pintype "passive"))
      (node (ref "R4") (pin "1") (pinfunction "1_1") (pintype "passive"))
      (node (ref "R5") (pin "1") (pinfunction "1_1") (pintype "passive"))
      (node (ref "R6") (pin "1") (pinfunction "1_1") (pintype "passive"))
      (node (ref "U3") (pin "1") (pinfunction "BIAS_1") (pintype "passive"))
    )
    (net (code "6") (name "+5V-CON") (class "Default")
      (node (ref "J4") (pin "1") (pinfunction "VUSB_1") (pintype "passive"))
      (node (ref "R7") (pin "1") (pinfunction "1_1") (pintype "passive"))
    )
    (net (code "7") (name "1N") (class "Default")
      (node (ref "J12") (pin "GND") (pinfunction "GND_GND") (pintype "bidirectional"))
      (node (ref "J12") (pin "GNDBREAK") (pinfunction "GNDBREAK_GNDBREAK") (pintype "bidirectional"))
      (node (ref "R45") (pin "1") (pinfunction "1_1") (pintype "passive"))
      (node (ref "U9") (pin "4") (pinfunction "IO3_4") (pintype "bidirectional"))
    )
    (net (code "8") (name "1P") (class "Default")
      (node (ref "J12") (pin "PWR") (pinfunction "PWR_PWR") (pintype "bidirectional"))
      (node (ref "R45") (pin "2") (pinfunction "2_2") (pintype "passive"))
      (node (ref "U10") (pin "1") (pinfunction "IO1_1") (pintype "bidirectional"))
    )
    (net (code "9") (name "2N") (class "Default")
      (node (ref "J11") (pin "GND") (pinfunction "GND_GND") (pintype "bidirectional"))
      (node (ref "J11") (pin "GNDBREAK") (pinfunction "GNDBREAK_GNDBREAK") (pintype "bidirectional"))
      (node (ref "RA4") (pin "3") (pinfunction "3_3") (pintype "passive"))
      (node (ref "U9") (pin "2") (pinfunction "IO2_2") (pintype "bidirectional"))
    )
    (net (code "10") (name "2P") (class "Default")
      (node (ref "J11") (pin "PWR") (pinfunction "PWR_PWR") (pintype "bidirectional"))
      (node (ref "RA4") (pin "4") (pinfunction "4_4") (pintype "passive"))
      (node (ref "U9") (pin "5") (pinfunction "IO4_5") (pintype "bidirectional"))
    )
    (net (code "11") (name "3N") (class "Default")
      (node (ref "J10") (pin "GND") (pinfunction "GND_GND") (pintype "bidirectional"))
      (node (ref "J10") (pin "GNDBREAK") (pinfunction "GNDBREAK_GNDBREAK") (pintype "bidirectional"))
      (node (ref "RA4") (pin "1") (pinfunction "1_1") (pintype "passive"))
      (node (ref "U8") (pin "4") (pinfunction "IO3_4") (pintype "bidirectional"))
    )
    (net (code "12") (name "3P") (class "Default")
      (node (ref "J10") (pin "PWR") (pinfunction "PWR_PWR") (pintype "bidirectional"))
      (node (ref "RA4") (pin "2") (pinfunction "2_2") (pintype "passive"))
      (node (ref "U9") (pin "1") (pinfunction "IO1_1") (pintype "bidirectional"))
    )
    (net (code "13") (name "4N") (class "Default")
      (node (ref "J9") (pin "GND") (pinfunction "GND_GND") (pintype "bidirectional"))
      (node (ref "J9") (pin "GNDBREAK") (pinfunction "GNDBREAK_GNDBREAK") (pintype "bidirectional"))
      (node (ref "RA3") (pin "3") (pinfunction "3_3") (pintype "passive"))
      (node (ref "U8") (pin "2") (pinfunction "IO2_2") (pintype "bidirectional"))
    )
    (net (code "14") (name "4P") (class "Default")
      (node (ref "J9") (pin "PWR") (pinfunction "PWR_PWR") (pintype "bidirectional"))
      (node (ref "RA3") (pin "4") (pinfunction "4_4") (pintype "passive"))
      (node (ref "U8") (pin "5") (pinfunction "IO4_5") (pintype "bidirectional"))
    )
    (net (code "15") (name "5N") (class "Default")
      (node (ref "J8") (pin "GND") (pinfunction "GND_GND") (pintype "bidirectional"))
      (node (ref "J8") (pin "GNDBREAK") (pinfunction "GNDBREAK_GNDBREAK") (pintype "bidirectional"))
      (node (ref "RA3") (pin "1") (pinfunction "1_1") (pintype "passive"))
      (node (ref "U7") (pin "4") (pinfunction "IO3_4") (pintype "bidirectional"))
    )
    (net (code "16") (name "5P") (class "Default")
      (node (ref "J8") (pin "PWR") (pinfunction "PWR_PWR") (pintype "bidirectional"))
      (node (ref "RA3") (pin "2") (pinfunction "2_2") (pintype "passive"))
      (node (ref "U8") (pin "1") (pinfunction "IO1_1") (pintype "bidirectional"))
    )
    (net (code "17") (name "5V_USB") (class "Default")
      (node (ref "U4") (pin "4") (pinfunction "G_4") (pintype "passive"))
    )
    (net (code "18") (name "6N") (class "Default")
      (node (ref "J7") (pin "GND") (pinfunction "GND_GND") (pintype "bidirectional"))
      (node (ref "J7") (pin "GNDBREAK") (pinfunction "GNDBREAK_GNDBREAK") (pintype "bidirectional"))
      (node (ref "RA2") (pin "3") (pinfunction "3_3") (pintype "passive"))
      (node (ref "U7") (pin "2") (pinfunction "IO2_2") (pintype "bidirectional"))
    )
    (net (code "19") (name "6P") (class "Default")
      (node (ref "J7") (pin "PWR") (pinfunction "PWR_PWR") (pintype "bidirectional"))
      (node (ref "RA2") (pin "4") (pinfunction "4_4") (pintype "passive"))
      (node (ref "U7") (pin "5") (pinfunction "IO4_5") (pintype "bidirectional"))
    )
    (net (code "20") (name "7N") (class "Default")
      (node (ref "J6") (pin "GND") (pinfunction "GND_GND") (pintype "bidirectional"))
      (node (ref "J6") (pin "GNDBREAK") (pinfunction "GNDBREAK_GNDBREAK") (pintype "bidirectional"))
      (node (ref "RA2") (pin "1") (pinfunction "1_1") (pintype "passive"))
      (node (ref "U6") (pin "4") (pinfunction "IO3_4") (pintype "bidirectional"))
    )
    (net (code "21") (name "7P") (class "Default")
      (node (ref "J6") (pin "PWR") (pinfunction "PWR_PWR") (pintype "bidirectional"))
      (node (ref "RA2") (pin "2") (pinfunction "2_2") (pintype "passive"))
      (node (ref "U7") (pin "1") (pinfunction "IO1_1") (pintype "bidirectional"))
    )
    (net (code "22") (name "8N") (class "Default")
      (node (ref "J5") (pin "GND") (pinfunction "GND_GND") (pintype "bidirectional"))
      (node (ref "J5") (pin "GNDBREAK") (pinfunction "GNDBREAK_GNDBREAK") (pintype "bidirectional"))
      (node (ref "RA1") (pin "3") (pinfunction "3_3") (pintype "passive"))
      (node (ref "U6") (pin "2") (pinfunction "IO2_2") (pintype "bidirectional"))
    )
    (net (code "23") (name "8P") (class "Default")
      (node (ref "J5") (pin "PWR") (pinfunction "PWR_PWR") (pintype "bidirectional"))
      (node (ref "RA1") (pin "4") (pinfunction "4_4") (pintype "passive"))
      (node (ref "U6") (pin "5") (pinfunction "IO4_5") (pintype "bidirectional"))
    )
    (net (code "24") (name "9N") (class "Default")
      (node (ref "J20") (pin "GND") (pinfunction "GND_GND") (pintype "bidirectional"))
      (node (ref "J20") (pin "GNDBREAK") (pinfunction "GNDBREAK_GNDBREAK") (pintype "bidirectional"))
      (node (ref "R14") (pin "1") (pinfunction "1_1") (pintype "passive"))
      (node (ref "U15") (pin "4") (pinfunction "IO3_4") (pintype "bidirectional"))
    )
    (net (code "25") (name "9P") (class "Default")
      (node (ref "J20") (pin "PWR") (pinfunction "PWR_PWR") (pintype "bidirectional"))
      (node (ref "R14") (pin "2") (pinfunction "2_2") (pintype "passive"))
      (node (ref "U16") (pin "1") (pinfunction "IO1_1") (pintype "bidirectional"))
    )
    (net (code "26") (name "10N") (class "Default")
      (node (ref "J19") (pin "GND") (pinfunction "GND_GND") (pintype "bidirectional"))
      (node (ref "J19") (pin "GNDBREAK") (pinfunction "GNDBREAK_GNDBREAK") (pintype "bidirectional"))
      (node (ref "RA8") (pin "3") (pinfunction "3_3") (pintype "passive"))
      (node (ref "U15") (pin "2") (pinfunction "IO2_2") (pintype "bidirectional"))
    )
    (net (code "27") (name "10P") (class "Default")
      (node (ref "J19") (pin "PWR") (pinfunction "PWR_PWR") (pintype "bidirectional"))
      (node (ref "RA8") (pin "4") (pinfunction "4_4") (pintype "passive"))
      (node (ref "U15") (pin "5") (pinfunction "IO4_5") (pintype "bidirectional"))
    )
    (net (code "28") (name "11N") (class "Default")
      (node (ref "J18") (pin "GND") (pinfunction "GND_GND") (pintype "bidirectional"))
      (node (ref "J18") (pin "GNDBREAK") (pinfunction "GNDBREAK_GNDBREAK") (pintype "bidirectional"))
      (node (ref "RA8") (pin "1") (pinfunction "1_1") (pintype "passive"))
      (node (ref "U14") (pin "4") (pinfunction "IO3_4") (pintype "bidirectional"))
    )
    (net (code "29") (name "11P") (class "Default")
      (node (ref "J18") (pin "PWR") (pinfunction "PWR_PWR") (pintype "bidirectional"))
      (node (ref "RA8") (pin "2") (pinfunction "2_2") (pintype "passive"))
      (node (ref "U15") (pin "1") (pinfunction "IO1_1") (pintype "bidirectional"))
    )
    (net (code "30") (name "12N") (class "Default")
      (node (ref "J17") (pin "GND") (pinfunction "GND_GND") (pintype "bidirectional"))
      (node (ref "J17") (pin "GNDBREAK") (pinfunction "GNDBREAK_GNDBREAK") (pintype "bidirectional"))
      (node (ref "RA7") (pin "3") (pinfunction "3_3") (pintype "passive"))
      (node (ref "U14") (pin "2") (pinfunction "IO2_2") (pintype "bidirectional"))
    )
    (net (code "31") (name "12P") (class "Default")
      (node (ref "J17") (pin "PWR") (pinfunction "PWR_PWR") (pintype "bidirectional"))
      (node (ref "RA7") (pin "4") (pinfunction "4_4") (pintype "passive"))
      (node (ref "U14") (pin "5") (pinfunction "IO4_5") (pintype "bidirectional"))
    )
    (net (code "32") (name "13N") (class "Default")
      (node (ref "J16") (pin "GND") (pinfunction "GND_GND") (pintype "bidirectional"))
      (node (ref "J16") (pin "GNDBREAK") (pinfunction "GNDBREAK_GNDBREAK") (pintype "bidirectional"))
      (node (ref "RA7") (pin "1") (pinfunction "1_1") (pintype "passive"))
      (node (ref "U13") (pin "4") (pinfunction "IO3_4") (pintype "bidirectional"))
    )
    (net (code "33") (name "13P") (class "Default")
      (node (ref "J16") (pin "PWR") (pinfunction "PWR_PWR") (pintype "bidirectional"))
      (node (ref "RA7") (pin "2") (pinfunction "2_2") (pintype "passive"))
      (node (ref "U14") (pin "1") (pinfunction "IO1_1") (pintype "bidirectional"))
    )
    (net (code "34") (name "14N") (class "Default")
      (node (ref "J15") (pin "GND") (pinfunction "GND_GND") (pintype "bidirectional"))
      (node (ref "J15") (pin "GNDBREAK") (pinfunction "GNDBREAK_GNDBREAK") (pintype "bidirectional"))
      (node (ref "RA6") (pin "3") (pinfunction "3_3") (pintype "passive"))
      (node (ref "U13") (pin "2") (pinfunction "IO2_2") (pintype "bidirectional"))
    )
    (net (code "35") (name "14P") (class "Default")
      (node (ref "J15") (pin "PWR") (pinfunction "PWR_PWR") (pintype "bidirectional"))
      (node (ref "RA6") (pin "4") (pinfunction "4_4") (pintype "passive"))
      (node (ref "U13") (pin "5") (pinfunction "IO4_5") (pintype "bidirectional"))
    )
    (net (code "36") (name "15N") (class "Default")
      (node (ref "J14") (pin "GND") (pinfunction "GND_GND") (pintype "bidirectional"))
      (node (ref "J14") (pin "GNDBREAK") (pinfunction "GNDBREAK_GNDBREAK") (pintype "bidirectional"))
      (node (ref "RA6") (pin "1") (pinfunction "1_1") (pintype "passive"))
      (node (ref "U12") (pin "4") (pinfunction "IO3_4") (pintype "bidirectional"))
    )
    (net (code "37") (name "15P") (class "Default")
      (node (ref "J14") (pin "PWR") (pinfunction "PWR_PWR") (pintype "bidirectional"))
      (node (ref "RA6") (pin "2") (pinfunction "2_2") (pintype "passive"))
      (node (ref "U13") (pin "1") (pinfunction "IO1_1") (pintype "bidirectional"))
    )
    (net (code "38") (name "16N") (class "Default")
      (node (ref "J13") (pin "GND") (pinfunction "GND_GND") (pintype "bidirectional"))
      (node (ref "J13") (pin "GNDBREAK") (pinfunction "GNDBREAK_GNDBREAK") (pintype "bidirectional"))
      (node (ref "RA5") (pin "3") (pinfunction "3_3") (pintype "passive"))
      (node (ref "U12") (pin "2") (pinfunction "IO2_2") (pintype "bidirectional"))
    )
    (net (code "39") (name "16P") (class "Default")
      (node (ref "J13") (pin "PWR") (pinfunction "PWR_PWR") (pintype "bidirectional"))
      (node (ref "RA5") (pin "4") (pinfunction "4_4") (pintype "passive"))
      (node (ref "U12") (pin "5") (pinfunction "IO4_5") (pintype "bidirectional"))
    )
    (net (code "40") (name "AIN1N") (class "Default")
      (node (ref "CA5") (pin "8") (pinfunction "8_8") (pintype "passive"))
      (node (ref "R45") (pin "8") (pinfunction "8_8") (pintype "passive"))
      (node (ref "U1") (pin "15") (pinfunction "IN1N_15") (pintype "input"))
    )
    (net (code "41") (name "AIN1P") (class "Default")
      (node (ref "CA5") (pin "7") (pinfunction "7_7") (pintype "passive"))
      (node (ref "R45") (pin "7") (pinfunction "7_7") (pintype "passive"))
      (node (ref "U1") (pin "16") (pinfunction "IN1P_16") (pintype "input"))
    )
    (net (code "42") (name "AIN2N") (class "Default")
      (node (ref "CA4") (pin "6") (pinfunction "6_6") (pintype "passive"))
      (node (ref "RA4") (pin "6") (pinfunction "6_6") (pintype "passive"))
      (node (ref "U1") (pin "13") (pinfunction "IN2N_13") (pintype "input"))
    )
    (net (code "43") (name "AIN2P") (class "Default")
      (node (ref "CA4") (pin "5") (pinfunction "5_5") (pintype "passive"))
      (node (ref "RA4") (pin "5") (pinfunction "5_5") (pintype "passive"))
      (node (ref "U1") (pin "14") (pinfunction "IN2P_14") (pintype "input"))
    )
    (net (code "44") (name "AIN3N") (class "Default")
      (node (ref "CA4") (pin "8") (pinfunction "8_8") (pintype "passive"))
      (node (ref "RA4") (pin "8") (pinfunction "8_8") (pintype "passive"))
      (node (ref "U1") (pin "11") (pinfunction "IN3N_11") (pintype "input"))
    )
    (net (code "45") (name "AIN3P") (class "Default")
      (node (ref "CA4") (pin "7") (pinfunction "7_7") (pintype "passive"))
      (node (ref "RA4") (pin "7") (pinfunction "7_7") (pintype "passive"))
      (node (ref "U1") (pin "12") (pinfunction "IN3P_12") (pintype "input"))
    )
    (net (code "46") (name "AIN4N") (class "Default")
      (node (ref "CA3") (pin "6") (pinfunction "6_6") (pintype "passive"))
      (node (ref "RA3") (pin "6") (pinfunction "6_6") (pintype "passive"))
      (node (ref "U1") (pin "9") (pinfunction "IN4N_9") (pintype "input"))
    )
    (net (code "47") (name "AIN4P") (class "Default")
      (node (ref "CA3") (pin "5") (pinfunction "5_5") (pintype "passive"))
      (node (ref "RA3") (pin "5") (pinfunction "5_5") (pintype "passive"))
      (node (ref "U1") (pin "10") (pinfunction "IN4P_10") (pintype "input"))
    )
    (net (code "48") (name "AIN5N") (class "Default")
      (node (ref "CA3") (pin "8") (pinfunction "8_8") (pintype "passive"))
      (node (ref "RA3") (pin "8") (pinfunction "8_8") (pintype "passive"))
      (node (ref "U1") (pin "7") (pinfunction "IN5N_7") (pintype "input"))
    )
    (net (code "49") (name "AIN5P") (class "Default")
      (node (ref "CA3") (pin "7") (pinfunction "7_7") (pintype "passive"))
      (node (ref "RA3") (pin "7") (pinfunction "7_7") (pintype "passive"))
      (node (ref "U1") (pin "8") (pinfunction "IN5P_8") (pintype "input"))
    )
    (net (code "50") (name "AIN6N") (class "Default")
      (node (ref "CA2") (pin "6") (pinfunction "6_6") (pintype "passive"))
      (node (ref "RA2") (pin "6") (pinfunction "6_6") (pintype "passive"))
      (node (ref "U1") (pin "5") (pinfunction "IN6N_5") (pintype "input"))
    )
    (net (code "51") (name "AIN6P") (class "Default")
      (node (ref "CA2") (pin "5") (pinfunction "5_5") (pintype "passive"))
      (node (ref "RA2") (pin "5") (pinfunction "5_5") (pintype "passive"))
      (node (ref "U1") (pin "6") (pinfunction "IN6P_6") (pintype "input"))
    )
    (net (code "52") (name "AIN7N") (class "Default")
      (node (ref "CA2") (pin "8") (pinfunction "8_8") (pintype "passive"))
      (node (ref "RA2") (pin "8") (pinfunction "8_8") (pintype "passive"))
      (node (ref "U1") (pin "3") (pinfunction "IN7N_3") (pintype "input"))
    )
    (net (code "53") (name "AIN7P") (class "Default")
      (node (ref "CA2") (pin "7") (pinfunction "7_7") (pintype "passive"))
      (node (ref "RA2") (pin "7") (pinfunction "7_7") (pintype "passive"))
      (node (ref "U1") (pin "4") (pinfunction "IN7P_4") (pintype "input"))
    )
    (net (code "54") (name "AIN8N") (class "Default")
      (node (ref "CA1") (pin "6") (pinfunction "6_6") (pintype "passive"))
      (node (ref "RA1") (pin "6") (pinfunction "6_6") (pintype "passive"))
      (node (ref "U1") (pin "1") (pinfunction "IN8N_1") (pintype "input"))
    )
    (net (code "55") (name "AIN8P") (class "Default")
      (node (ref "CA1") (pin "5") (pinfunction "5_5") (pintype "passive"))
      (node (ref "RA1") (pin "5") (pinfunction "5_5") (pintype "passive"))
      (node (ref "U1") (pin "2") (pinfunction "IN8P_2") (pintype "input"))
    )
    (net (code "56") (name "AIN9N") (class "Default")
      (node (ref "CA10") (pin "8") (pinfunction "8_8") (pintype "passive"))
      (node (ref "R14") (pin "8") (pinfunction "8_8") (pintype "passive"))
      (node (ref "U2") (pin "15") (pinfunction "IN1N_15") (pintype "input"))
    )
    (net (code "57") (name "AIN9P") (class "Default")
      (node (ref "CA10") (pin "7") (pinfunction "7_7") (pintype "passive"))
      (node (ref "R14") (pin "7") (pinfunction "7_7") (pintype "passive"))
      (node (ref "U2") (pin "16") (pinfunction "IN1P_16") (pintype "input"))
    )
    (net (code "58") (name "AIN10N") (class "Default")
      (node (ref "CA9") (pin "6") (pinfunction "6_6") (pintype "passive"))
      (node (ref "RA8") (pin "6") (pinfunction "6_6") (pintype "passive"))
      (node (ref "U2") (pin "13") (pinfunction "IN2N_13") (pintype "input"))
    )
    (net (code "59") (name "AIN10P") (class "Default")
      (node (ref "CA9") (pin "5") (pinfunction "5_5") (pintype "passive"))
      (node (ref "RA8") (pin "5") (pinfunction "5_5") (pintype "passive"))
      (node (ref "U2") (pin "14") (pinfunction "IN2P_14") (pintype "input"))
    )
    (net (code "60") (name "AIN11N") (class "Default")
      (node (ref "CA9") (pin "8") (pinfunction "8_8") (pintype "passive"))
      (node (ref "RA8") (pin "8") (pinfunction "8_8") (pintype "passive"))
      (node (ref "U2") (pin "11") (pinfunction "IN3N_11") (pintype "input"))
    )
    (net (code "61") (name "AIN11P") (class "Default")
      (node (ref "CA9") (pin "7") (pinfunction "7_7") (pintype "passive"))
      (node (ref "RA8") (pin "7") (pinfunction "7_7") (pintype "passive"))
      (node (ref "U2") (pin "12") (pinfunction "IN3P_12") (pintype "input"))
    )
    (net (code "62") (name "AIN12N") (class "Default")
      (node (ref "CA8") (pin "6") (pinfunction "6_6") (pintype "passive"))
      (node (ref "RA7") (pin "6") (pinfunction "6_6") (pintype "passive"))
      (node (ref "U2") (pin "9") (pinfunction "IN4N_9") (pintype "input"))
    )
    (net (code "63") (name "AIN12P") (class "Default")
      (node (ref "CA8") (pin "5") (pinfunction "5_5") (pintype "passive"))
      (node (ref "RA7") (pin "5") (pinfunction "5_5") (pintype "passive"))
      (node (ref "U2") (pin "10") (pinfunction "IN4P_10") (pintype "input"))
    )
    (net (code "64") (name "AIN13N") (class "Default")
      (node (ref "CA8") (pin "8") (pinfunction "8_8") (pintype "passive"))
      (node (ref "RA7") (pin "8") (pinfunction "8_8") (pintype "passive"))
      (node (ref "U2") (pin "7") (pinfunction "IN5N_7") (pintype "input"))
    )
    (net (code "65") (name "AIN13P") (class "Default")
      (node (ref "CA8") (pin "7") (pinfunction "7_7") (pintype "passive"))
      (node (ref "RA7") (pin "7") (pinfunction "7_7") (pintype "passive"))
      (node (ref "U2") (pin "8") (pinfunction "IN5P_8") (pintype "input"))
    )
    (net (code "66") (name "AIN14N") (class "Default")
      (node (ref "CA7") (pin "6") (pinfunction "6_6") (pintype "passive"))
      (node (ref "RA6") (pin "6") (pinfunction "6_6") (pintype "passive"))
      (node (ref "U2") (pin "5") (pinfunction "IN6N_5") (pintype "input"))
    )
    (net (code "67") (name "AIN14P") (class "Default")
      (node (ref "CA7") (pin "5") (pinfunction "5_5") (pintype "passive"))
      (node (ref "RA6") (pin "5") (pinfunction "5_5") (pintype "passive"))
      (node (ref "U2") (pin "6") (pinfunction "IN6P_6") (pintype "input"))
    )
    (net (code "68") (name "AIN15N") (class "Default")
      (node (ref "CA7") (pin "8") (pinfunction "8_8") (pintype "passive"))
      (node (ref "RA6") (pin "8") (pinfunction "8_8") (pintype "passive"))
      (node (ref "U2") (pin "3") (pinfunction "IN7N_3") (pintype "input"))
    )
    (net (code "69") (name "AIN15P") (class "Default")
      (node (ref "CA7") (pin "7") (pinfunction "7_7") (pintype "passive"))
      (node (ref "RA6") (pin "7") (pinfunction "7_7") (pintype "passive"))
      (node (ref "U2") (pin "4") (pinfunction "IN7P_4") (pintype "input"))
    )
    (net (code "70") (name "AIN16N") (class "Default")
      (node (ref "CA6") (pin "6") (pinfunction "6_6") (pintype "passive"))
      (node (ref "RA5") (pin "6") (pinfunction "6_6") (pintype "passive"))
      (node (ref "U2") (pin "1") (pinfunction "IN8N_1") (pintype "input"))
    )
    (net (code "71") (name "AIN16P") (class "Default")
      (node (ref "CA6") (pin "5") (pinfunction "5_5") (pintype "passive"))
      (node (ref "RA5") (pin "5") (pinfunction "5_5") (pintype "passive"))
      (node (ref "U2") (pin "2") (pinfunction "IN8P_2") (pintype "input"))
    )
    (net (code "72") (name "BATT_SWITCH") (class "Default")
      (node (ref "C4") (pin "1") (pinfunction "1_1") (pintype "passive"))
      (node (ref "C5") (pin "1") (pinfunction "1_1") (pintype "passive"))
      (node (ref "C6") (pin "1") (pinfunction "1_1") (pintype "passive"))
      (node (ref "C7") (pin "1") (pinfunction "1_1") (pintype "passive"))
      (node (ref "R1") (pin "2") (pinfunction "2_2") (pintype "passive"))
      (node (ref "R8") (pin "1") (pinfunction "1_1") (pintype "passive"))
      (node (ref "SW1") (pin "3") (pinfunction "3_3") (pintype "passive"))
      (node (ref "U3") (pin "12") (pinfunction "VIN2_12") (pintype "input"))
      (node (ref "U3") (pin "8") (pinfunction "VIN1_8") (pintype "input"))
    )
    (net (code "73") (name "BIAS") (class "Default")
      (node (ref "C25") (pin "2") (pinfunction "2_2") (pintype "passive"))
      (node (ref "J21") (pin "GND") (pinfunction "GND_GND") (pintype "bidirectional"))
      (node (ref "J21") (pin "GNDBREAK") (pinfunction "GNDBREAK_GNDBREAK") (pintype "bidirectional"))
      (node (ref "J21") (pin "PWR") (pinfunction "PWR_PWR") (pintype "bidirectional"))
      (node (ref "R12") (pin "2") (pinfunction "2_2") (pintype "passive"))
      (node (ref "RA1") (pin "1") (pinfunction "1_1") (pintype "passive"))
      (node (ref "U1") (pin "62") (pinfunction "BIASIN_62") (pintype "input"))
      (node (ref "U1") (pin "63") (pinfunction "BIASOUT_63") (pintype "output"))
      (node (ref "U11") (pin "4") (pinfunction "IO3_4") (pintype "bidirectional"))
    )
    (net (code "74") (name "BIAS_1") (class "Default")
      (node (ref "J23") (pin "GND") (pinfunction "GND_GND") (pintype "bidirectional"))
      (node (ref "J23") (pin "GNDBREAK") (pinfunction "GNDBREAK_GNDBREAK") (pintype "bidirectional"))
      (node (ref "J23") (pin "PWR") (pinfunction "PWR_PWR") (pintype "bidirectional"))
      (node (ref "RA5") (pin "1") (pinfunction "1_1") (pintype "passive"))
      (node (ref "U17") (pin "4") (pinfunction "IO3_4") (pintype "bidirectional"))
    )
    (net (code "75") (name "BIAS_DRV") (class "Default")
      (node (ref "C25") (pin "1") (pinfunction "1_1") (pintype "passive"))
      (node (ref "CA1") (pin "8") (pinfunction "8_8") (pintype "passive"))
      (node (ref "R12") (pin "1") (pinfunction "1_1") (pintype "passive"))
      (node (ref "RA1") (pin "8") (pinfunction "8_8") (pintype "passive"))
    )
    (net (code "76") (name "BIAS_DRV_1") (class "Default")
      (node (ref "C37") (pin "1") (pinfunction "1_1") (pintype "passive"))
      (node (ref "CA6") (pin "8") (pinfunction "8_8") (pintype "passive"))
      (node (ref "R13") (pin "1") (pinfunction "1_1") (pintype "passive"))
      (node (ref "RA5") (pin "8") (pinfunction "8_8") (pintype "passive"))
    )
    (net (code "77") (name "BIAS_INV") (class "Default")
      (node (ref "J29") (pin "1") (pinfunction "1_1") (pintype "passive"))
      (node (ref "U1") (pin "61") (pinfunction "BIASINV_61") (pintype "bidirectional"))
    )
    (net (code "78") (name "BIAS_INV_1") (class "Default")
      (node (ref "U2") (pin "61") (pinfunction "BIASINV_61") (pintype "bidirectional"))
    )
    (net (code "79") (name "CLK_ADS") (class "Default")
      (node (ref "U1") (pin "37") (pinfunction "CLK_37") (pintype "input"))
      (node (ref "U2") (pin "37") (pinfunction "CLK_37") (pintype "input"))
    )
    (net (code "80") (name "GND") (class "Default")
      (node (ref "A1") (pin "GND") (pinfunction "GND_GND") (pintype "passive"))
      (node (ref "C1") (pin "2") (pinfunction "2_2") (pintype "passive"))
      (node (ref "C11") (pin "2") (pinfunction "2_2") (pintype "passive"))
      (node (ref "C12") (pin "2") (pinfunction "2_2") (pintype "passive"))
      (node (ref "C13") (pin "2") (pinfunction "2_2") (pintype "passive"))
      (node (ref "C14") (pin "2") (pinfunction "2_2") (pintype "passive"))
      (node (ref "C15") (pin "2") (pinfunction "2_2") (pintype "passive"))
      (node (ref "C16") (pin "2") (pinfunction "2_2") (pintype "passive"))
      (node (ref "C17") (pin "2") (pinfunction "2_2") (pintype "passive"))
      (node (ref "C18") (pin "2") (pinfunction "2_2") (pintype "passive"))
      (node (ref "C19") (pin "2") (pinfunction "2_2") (pintype "passive"))
      (node (ref "C2") (pin "2") (pinfunction "2_2") (pintype "passive"))
      (node (ref "C20") (pin "2") (pinfunction "2_2") (pintype "passive"))
      (node (ref "C21") (pin "2") (pinfunction "2_2") (pintype "passive"))
      (node (ref "C22") (pin "2") (pinfunction "2_2") (pintype "passive"))
      (node (ref "C23") (pin "2") (pinfunction "2_2") (pintype "passive"))
      (node (ref "C24") (pin "2") (pinfunction "2_2") (pintype "passive"))
      (node (ref "C26") (pin "2") (pinfunction "2_2") (pintype "passive"))
      (node (ref "C27") (pin "2") (pinfunction "2_2") (pintype "passive"))
      (node (ref "C28") (pin "2") (pinfunction "2_2") (pintype "passive"))
      (node (ref "C29") (pin "2") (pinfunction "2_2") (pintype "passive"))
      (node (ref "C3") (pin "2") (pinfunction "2_2") (pintype "passive"))
      (node (ref "C30") (pin "2") (pinfunction "2_2") (pintype "passive"))
      (node (ref "C31") (pin "2") (pinfunction "2_2") (pintype "passive"))
      (node (ref "C32") (pin "2") (pinfunction "2_2") (pintype "passive"))
      (node (ref "C33") (pin "2") (pinfunction "2_2") (pintype "passive"))
      (node (ref "C34") (pin "2") (pinfunction "2_2") (pintype "passive"))
      (node (ref "C35") (pin "2") (pinfunction "2_2") (pintype "passive"))
      (node (ref "C36") (pin "2") (pinfunction "2_2") (pintype "passive"))
      (node (ref "C4") (pin "2") (pinfunction "2_2") (pintype "passive"))
      (node (ref "C5") (pin "2") (pinfunction "2_2") (pintype "passive"))
      (node (ref "C6") (pin "2") (pinfunction "2_2") (pintype "passive"))
      (node (ref "C7") (pin "2") (pinfunction "2_2") (pintype "passive"))
      (node (ref "C9") (pin "2") (pinfunction "2_2") (pintype "passive"))
      (node (ref "CA1") (pin "1") (pinfunction "1_1") (pintype "passive"))
      (node (ref "CA1") (pin "2") (pinfunction "2_2") (pintype "passive"))
      (node (ref "CA1") (pin "3") (pinfunction "3_3") (pintype "passive"))
      (node (ref "CA1") (pin "4") (pinfunction "4_4") (pintype "passive"))
      (node (ref "CA1") (pin "7") (pinfunction "7_7") (pintype "passive"))
      (node (ref "CA10") (pin "1") (pinfunction "1_1") (pintype "passive"))
      (node (ref "CA10") (pin "2") (pinfunction "2_2") (pintype "passive"))
      (node (ref "CA10") (pin "3") (pinfunction "3_3") (pintype "passive"))
      (node (ref "CA10") (pin "4") (pinfunction "4_4") (pintype "passive"))
      (node (ref "CA2") (pin "1") (pinfunction "1_1") (pintype "passive"))
      (node (ref "CA2") (pin "2") (pinfunction "2_2") (pintype "passive"))
      (node (ref "CA2") (pin "3") (pinfunction "3_3") (pintype "passive"))
      (node (ref "CA2") (pin "4") (pinfunction "4_4") (pintype "passive"))
      (node (ref "CA3") (pin "1") (pinfunction "1_1") (pintype "passive"))
      (node (ref "CA3") (pin "2") (pinfunction "2_2") (pintype "passive"))
      (node (ref "CA3") (pin "3") (pinfunction "3_3") (pintype "passive"))
      (node (ref "CA3") (pin "4") (pinfunction "4_4") (pintype "passive"))
      (node (ref "CA4") (pin "1") (pinfunction "1_1") (pintype "passive"))
      (node (ref "CA4") (pin "2") (pinfunction "2_2") (pintype "passive"))
      (node (ref "CA4") (pin "3") (pinfunction "3_3") (pintype "passive"))
      (node (ref "CA4") (pin "4") (pinfunction "4_4") (pintype "passive"))
      (node (ref "CA5") (pin "1") (pinfunction "1_1") (pintype "passive"))
      (node (ref "CA5") (pin "2") (pinfunction "2_2") (pintype "passive"))
      (node (ref "CA5") (pin "3") (pinfunction "3_3") (pintype "passive"))
      (node (ref "CA5") (pin "4") (pinfunction "4_4") (pintype "passive"))
      (node (ref "CA6") (pin "1") (pinfunction "1_1") (pintype "passive"))
      (node (ref "CA6") (pin "2") (pinfunction "2_2") (pintype "passive"))
      (node (ref "CA6") (pin "3") (pinfunction "3_3") (pintype "passive"))
      (node (ref "CA6") (pin "4") (pinfunction "4_4") (pintype "passive"))
      (node (ref "CA6") (pin "7") (pinfunction "7_7") (pintype "passive"))
      (node (ref "CA7") (pin "1") (pinfunction "1_1") (pintype "passive"))
      (node (ref "CA7") (pin "2") (pinfunction "2_2") (pintype "passive"))
      (node (ref "CA7") (pin "3") (pinfunction "3_3") (pintype "passive"))
      (node (ref "CA7") (pin "4") (pinfunction "4_4") (pintype "passive"))
      (node (ref "CA8") (pin "1") (pinfunction "1_1") (pintype "passive"))
      (node (ref "CA8") (pin "2") (pinfunction "2_2") (pintype "passive"))
      (node (ref "CA8") (pin "3") (pinfunction "3_3") (pintype "passive"))
      (node (ref "CA8") (pin "4") (pinfunction "4_4") (pintype "passive"))
      (node (ref "CA9") (pin "1") (pinfunction "1_1") (pintype "passive"))
      (node (ref "CA9") (pin "2") (pinfunction "2_2") (pintype "passive"))
      (node (ref "CA9") (pin "3") (pinfunction "3_3") (pintype "passive"))
      (node (ref "CA9") (pin "4") (pinfunction "4_4") (pintype "passive"))
      (node (ref "D1") (pin "C") (pinfunction "C_C") (pintype "passive"))
      (node (ref "D2") (pin "C") (pinfunction "C_C") (pintype "passive"))
      (node (ref "D3") (pin "C") (pinfunction "C_C") (pintype "passive"))
      (node (ref "D4") (pin "C") (pinfunction "C_C") (pintype "passive"))
      (node (ref "J1") (pin "11") (pinfunction "11_11") (pintype "passive"))
      (node (ref "J1") (pin "12") (pinfunction "12_12") (pintype "passive"))
      (node (ref "J1") (pin "6") (pinfunction "6_6") (pintype "passive"))
      (node (ref "J25") (pin "1") (pinfunction "1_1") (pintype "passive"))
      (node (ref "J3") (pin "P$1") (pinfunction "1_P$1") (pintype "passive"))
      (node (ref "J30") (pin "1") (pinfunction "1_1") (pintype "passive"))
      (node (ref "J4") (pin "5") (pinfunction "GND_5") (pintype "passive"))
      (node (ref "J4") (pin "S1") (pinfunction "SHIELD_S1") (pintype "passive"))
      (node (ref "J4") (pin "S2") (pinfunction "SHIELD_S2") (pintype "passive"))
      (node (ref "J4") (pin "S3") (pinfunction "SHIELD_S3") (pintype "passive"))
      (node (ref "J4") (pin "S4") (pinfunction "SHIELD_S4") (pintype "passive"))
      (node (ref "J4") (pin "S5") (pinfunction "SHIELD_S5") (pintype "passive"))
      (node (ref "J4") (pin "S6") (pinfunction "SHIELD_S6") (pintype "passive"))
      (node (ref "R3") (pin "2") (pinfunction "2_2") (pintype "passive"))
      (node (ref "RA1") (pin "2") (pinfunction "2_2") (pintype "passive"))
      (node (ref "RA1") (pin "7") (pinfunction "7_7") (pintype "passive"))
      (node (ref "RA5") (pin "2") (pinfunction "2_2") (pintype "passive"))
      (node (ref "RA5") (pin "7") (pinfunction "7_7") (pintype "passive"))
      (node (ref "U1") (pin "20") (pinfunction "AVSS_2_20") (pintype "power_in"))
      (node (ref "U1") (pin "23") (pinfunction "AVSS_3_23") (pintype "power_in"))
      (node (ref "U1") (pin "25") (pinfunction "VREFN_25") (pintype "input"))
      (node (ref "U1") (pin "31") (pinfunction "RESV1_31") (pintype "input"))
      (node (ref "U1") (pin "32") (pinfunction "AVSS_4_32") (pintype "power_in"))
      (node (ref "U1") (pin "33") (pinfunction "DGND_2_33") (pintype "power_in"))
      (node (ref "U1") (pin "41") (pinfunction "DAISY_IN_41") (pintype "input"))
      (node (ref "U1") (pin "49") (pinfunction "DGND_3_49") (pintype "power_in"))
      (node (ref "U1") (pin "51") (pinfunction "DGND_51") (pintype "power_in"))
      (node (ref "U1") (pin "53") (pinfunction "AVSS1_53") (pintype "power_in"))
      (node (ref "U1") (pin "57") (pinfunction "AVSS_5_57") (pintype "power_in"))
      (node (ref "U1") (pin "58") (pinfunction "AVSS_58") (pintype "power_in"))
      (node (ref "U1") (pin "60") (pinfunction "BIASREF_60") (pintype "input"))
      (node (ref "U1") (pin "64") (pinfunction "RESERVED_64") (pintype "output"))
      (node (ref "U10") (pin "3") (pinfunction "GND_3") (pintype "power_in"))
      (node (ref "U11") (pin "1") (pinfunction "IO1_1") (pintype "bidirectional"))
      (node (ref "U11") (pin "3") (pinfunction "GND_3") (pintype "power_in"))
      (node (ref "U12") (pin "3") (pinfunction "GND_3") (pintype "power_in"))
      (node (ref "U13") (pin "3") (pinfunction "GND_3") (pintype "power_in"))
      (node (ref "U14") (pin "3") (pinfunction "GND_3") (pintype "power_in"))
      (node (ref "U15") (pin "3") (pinfunction "GND_3") (pintype "power_in"))
      (node (ref "U16") (pin "3") (pinfunction "GND_3") (pintype "power_in"))
      (node (ref "U17") (pin "1") (pinfunction "IO1_1") (pintype "bidirectional"))
      (node (ref "U17") (pin "3") (pinfunction "GND_3") (pintype "power_in"))
      (node (ref "U2") (pin "20") (pinfunction "AVSS_2_20") (pintype "power_in"))
      (node (ref "U2") (pin "23") (pinfunction "AVSS_3_23") (pintype "power_in"))
      (node (ref "U2") (pin "25") (pinfunction "VREFN_25") (pintype "input"))
      (node (ref "U2") (pin "31") (pinfunction "RESV1_31") (pintype "input"))
      (node (ref "U2") (pin "32") (pinfunction "AVSS_4_32") (pintype "power_in"))
      (node (ref "U2") (pin "33") (pinfunction "DGND_2_33") (pintype "power_in"))
      (node (ref "U2") (pin "41") (pinfunction "DAISY_IN_41") (pintype "input"))
      (node (ref "U2") (pin "49") (pinfunction "DGND_3_49") (pintype "power_in"))
      (node (ref "U2") (pin "51") (pinfunction "DGND_51") (pintype "power_in"))
      (node (ref "U2") (pin "53") (pinfunction "AVSS1_53") (pintype "power_in"))
      (node (ref "U2") (pin "57") (pinfunction "AVSS_5_57") (pintype "power_in"))
      (node (ref "U2") (pin "58") (pinfunction "AVSS_58") (pintype "power_in"))
      (node (ref "U2") (pin "60") (pinfunction "BIASREF_60") (pintype "input"))
      (node (ref "U2") (pin "64") (pinfunction "RESERVED_64") (pintype "output"))
      (node (ref "U3") (pin "11") (pinfunction "PGND2_11") (pintype "passive"))
      (node (ref "U3") (pin "3") (pinfunction "AGND_3") (pintype "passive"))
      (node (ref "U3") (pin "6") (pinfunction "MODE/SYNC_6") (pintype "passive"))
      (node (ref "U3") (pin "9") (pinfunction "PGND1_9") (pintype "passive"))
      (node (ref "U4") (pin "1") (pinfunction "S_1") (pintype "passive"))
      (node (ref "U4") (pin "2") (pinfunction "S_2") (pintype "passive"))
      (node (ref "U4") (pin "3") (pinfunction "S_3") (pintype "passive"))
      (node (ref "U5") (pin "2") (pinfunction "GND_2") (pintype "passive"))
      (node (ref "U6") (pin "3") (pinfunction "GND_3") (pintype "power_in"))
      (node (ref "U7") (pin "3") (pinfunction "GND_3") (pintype "power_in"))
      (node (ref "U8") (pin "3") (pinfunction "GND_3") (pintype "power_in"))
      (node (ref "U9") (pin "3") (pinfunction "GND_3") (pintype "power_in"))
    )
    (net (code "81") (name "MISO_ADS") (class "Default")
      (node (ref "A1") (pin "P$6") (pinfunction "P6_P$6") (pintype "passive"))
      (node (ref "U1") (pin "43") (pinfunction "DOUT_43") (pintype "output"))
      (node (ref "U2") (pin "43") (pinfunction "DOUT_43") (pintype "output"))
    )
    (net (code "82") (name "MISO_SD") (class "Default")
      (node (ref "A1") (pin "P$12") (pinfunction "P12_P$12") (pintype "passive"))
      (node (ref "J1") (pin "7") (pinfunction "7_7") (pintype "passive"))
    )
    (net (code "83") (name "MOSI_ADS") (class "Default")
      (node (ref "A1") (pin "P$5") (pinfunction "P5_P$5") (pintype "passive"))
      (node (ref "U1") (pin "34") (pinfunction "DIN_34") (pintype "input"))
      (node (ref "U2") (pin "34") (pinfunction "DIN_34") (pintype "input"))
    )
    (net (code "84") (name "MOSI_SD") (class "Default")
      (node (ref "A1") (pin "P$11") (pinfunction "P11_P$11") (pintype "passive"))
      (node (ref "J1") (pin "3") (pinfunction "3_3") (pintype "passive"))
    )
    (net (code "85") (name "Net-(C10-Pad1)") (class "Default")
      (node (ref "C10") (pin "1") (pinfunction "1_1") (pintype "passive"))
      (node (ref "R5") (pin "2") (pinfunction "2_2") (pintype "passive"))
    )
    (net (code "86") (name "Net-(D1-PadA)") (class "Default")
      (node (ref "D1") (pin "A") (pinfunction "A_A") (pintype "passive"))
      (node (ref "R8") (pin "2") (pinfunction "2_2") (pintype "passive"))
    )
    (net (code "87") (name "Net-(D2-PadA)") (class "Default")
      (node (ref "D2") (pin "A") (pinfunction "A_A") (pintype "passive"))
      (node (ref "R9") (pin "2") (pinfunction "2_2") (pintype "passive"))
    )
    (net (code "88") (name "Net-(D3-PadA)") (class "Default")
      (node (ref "D3") (pin "A") (pinfunction "A_A") (pintype "passive"))
      (node (ref "R10") (pin "2") (pinfunction "2_2") (pintype "passive"))
    )
    (net (code "89") (name "Net-(D4-PadA)") (class "Default")
      (node (ref "D4") (pin "A") (pinfunction "A_A") (pintype "passive"))
      (node (ref "R11") (pin "2") (pinfunction "2_2") (pintype "passive"))
    )
    (net (code "90") (name "Net-(J2-1)") (class "Default")
      (node (ref "J2") (pin "P$1") (pinfunction "1_P$1") (pintype "passive"))
      (node (ref "SW1") (pin "1") (pinfunction "1_1") (pintype "passive"))
    )
    (net (code "91") (name "Net-(U1-VCAP1)") (class "Default")
      (node (ref "C22") (pin "1") (pinfunction "1_1") (pintype "passive"))
      (node (ref "U1") (pin "28") (pinfunction "VCAP1_28") (pintype "passive"))
    )
    (net (code "92") (name "Net-(U1-VCAP2)") (class "Default")
      (node (ref "C21") (pin "1") (pinfunction "1_1") (pintype "passive"))
      (node (ref "U1") (pin "30") (pinfunction "VCAP2_30") (pintype "passive"))
    )
    (net (code "93") (name "Net-(U1-VCAP3)") (class "Default")
      (node (ref "C18") (pin "1") (pinfunction "1_1") (pintype "passive"))
      (node (ref "C19") (pin "1") (pinfunction "1_1") (pintype "passive"))
      (node (ref "U1") (pin "55") (pinfunction "VCAP3_55") (pintype "passive"))
    )
    (net (code "94") (name "Net-(U1-VCAP4)") (class "Default")
      (node (ref "C20") (pin "1") (pinfunction "1_1") (pintype "passive"))
      (node (ref "U1") (pin "26") (pinfunction "VCAP4_26") (pintype "output"))
    )
    (net (code "95") (name "Net-(U1-VREFP)") (class "Default")
      (node (ref "C23") (pin "1") (pinfunction "1_1") (pintype "passive"))
      (node (ref "C24") (pin "1") (pinfunction "1_1") (pintype "passive"))
      (node (ref "U1") (pin "24") (pinfunction "VREFP_24") (pintype "bidirectional"))
    )
    (net (code "96") (name "Net-(U2-BIASIN)") (class "Default")
      (node (ref "C37") (pin "2") (pinfunction "2_2") (pintype "passive"))
      (node (ref "R13") (pin "2") (pinfunction "2_2") (pintype "passive"))
      (node (ref "U2") (pin "62") (pinfunction "BIASIN_62") (pintype "input"))
      (node (ref "U2") (pin "63") (pinfunction "BIASOUT_63") (pintype "output"))
    )
    (net (code "97") (name "Net-(U2-VCAP1)") (class "Default")
      (node (ref "C34") (pin "1") (pinfunction "1_1") (pintype "passive"))
      (node (ref "U2") (pin "28") (pinfunction "VCAP1_28") (pintype "passive"))
    )
    (net (code "98") (name "Net-(U2-VCAP2)") (class "Default")
      (node (ref "C33") (pin "1") (pinfunction "1_1") (pintype "passive"))
      (node (ref "U2") (pin "30") (pinfunction "VCAP2_30") (pintype "passive"))
    )
    (net (code "99") (name "Net-(U2-VCAP3)") (class "Default")
      (node (ref "C30") (pin "1") (pinfunction "1_1") (pintype "passive"))
      (node (ref "C31") (pin "1") (pinfunction "1_1") (pintype "passive"))
      (node (ref "U2") (pin "55") (pinfunction "VCAP3_55") (pintype "passive"))
    )
    (net (code "100") (name "Net-(U2-VCAP4)") (class "Default")
      (node (ref "C32") (pin "1") (pinfunction "1_1") (pintype "passive"))
      (node (ref "U2") (pin "26") (pinfunction "VCAP4_26") (pintype "output"))
    )
    (net (code "101") (name "Net-(U2-VREFP)") (class "Default")
      (node (ref "C35") (pin "1") (pinfunction "1_1") (pintype "passive"))
      (node (ref "C36") (pin "1") (pinfunction "1_1") (pintype "passive"))
      (node (ref "U2") (pin "24") (pinfunction "VREFP_24") (pintype "bidirectional"))
    )
    (net (code "102") (name "Net-(U3-CBOOT)") (class "Default")
      (node (ref "C8") (pin "2") (pinfunction "2_2") (pintype "passive"))
      (node (ref "R2") (pin "1") (pinfunction "1_1") (pintype "passive"))
      (node (ref "U3") (pin "14") (pinfunction "CBOOT_14") (pintype "passive"))
    )
    (net (code "103") (name "Net-(U3-EN)") (class "Default")
      (node (ref "R1") (pin "1") (pinfunction "1_1") (pintype "passive"))
      (node (ref "U3") (pin "7") (pinfunction "EN_7") (pintype "passive"))
      (node (ref "U4") (pin "5") (pinfunction "D_5") (pintype "passive"))
      (node (ref "U4") (pin "6") (pinfunction "D_6") (pintype "passive"))
      (node (ref "U4") (pin "7") (pinfunction "D_7") (pintype "passive"))
      (node (ref "U4") (pin "8") (pinfunction "D_8") (pintype "passive"))
    )
    (net (code "104") (name "Net-(U3-FB)") (class "Default")
      (node (ref "C10") (pin "2") (pinfunction "2_2") (pintype "passive"))
      (node (ref "R3") (pin "1") (pinfunction "1_1") (pintype "passive"))
      (node (ref "R4") (pin "2") (pinfunction "2_2") (pintype "passive"))
      (node (ref "U3") (pin "4") (pinfunction "FB_4") (pintype "passive"))
    )
    (net (code "105") (name "Net-(U3-RBOOT)") (class "Default")
      (node (ref "R2") (pin "2") (pinfunction "2_2") (pintype "passive"))
      (node (ref "U3") (pin "13") (pinfunction "RBOOT_13") (pintype "passive"))
    )
    (net (code "106") (name "Net-(U3-SW)") (class "Default")
      (node (ref "C8") (pin "1") (pinfunction "1_1") (pintype "passive"))
      (node (ref "L1") (pin "1") (pinfunction "1_1") (pintype "passive"))
      (node (ref "U3") (pin "10") (pinfunction "SW_10") (pintype "passive"))
    )
    (net (code "107") (name "Net-(U3-VCC)") (class "Default")
      (node (ref "C9") (pin "1") (pinfunction "1_1") (pintype "passive"))
      (node (ref "U3") (pin "2") (pinfunction "VCC_2") (pintype "power_in"))
    )
    (net (code "108") (name "Net-(U5-BYPASS)") (class "Default")
      (node (ref "C12") (pin "1") (pinfunction "1_1") (pintype "passive"))
      (node (ref "U5") (pin "4") (pinfunction "BYPASS_4") (pintype "passive"))
    )
    (net (code "109") (name "SCK_SD") (class "Default")
      (node (ref "A1") (pin "P$13") (pinfunction "P13_P$13") (pintype "passive"))
      (node (ref "J1") (pin "5") (pinfunction "5_5") (pintype "passive"))
    )
    (net (code "110") (name "SCLK_ADS") (class "Default")
      (node (ref "A1") (pin "P$7") (pinfunction "P7_P$7") (pintype "passive"))
      (node (ref "U1") (pin "40") (pinfunction "SCLK_40") (pintype "input"))
      (node (ref "U2") (pin "40") (pinfunction "SCLK_40") (pintype "input"))
    )
    (net (code "111") (name "SCL_IMU") (class "Default")
      (node (ref "A1") (pin "P$27") (pinfunction "P27_P$27") (pintype "passive"))
      (node (ref "J28") (pin "1") (pinfunction "1_1") (pintype "passive"))
    )
    (net (code "112") (name "SDA_IMU") (class "Default")
      (node (ref "A1") (pin "P$28") (pinfunction "P28_P$28") (pintype "passive"))
      (node (ref "J27") (pin "1") (pinfunction "1_1") (pintype "passive"))
    )
    (net (code "113") (name "SRB1") (class "Default")
      (node (ref "CA5") (pin "5") (pinfunction "5_5") (pintype "passive"))
      (node (ref "R45") (pin "5") (pinfunction "5_5") (pintype "passive"))
      (node (ref "U1") (pin "17") (pinfunction "SRB1_17") (pintype "bidirectional"))
    )
    (net (code "114") (name "SRB1_1") (class "Default")
      (node (ref "CA10") (pin "5") (pinfunction "5_5") (pintype "passive"))
      (node (ref "R14") (pin "5") (pinfunction "5_5") (pintype "passive"))
      (node (ref "U2") (pin "17") (pinfunction "SRB1_17") (pintype "bidirectional"))
    )
    (net (code "115") (name "SRB1_OUT") (class "Default")
      (node (ref "J22") (pin "GND") (pinfunction "GND_GND") (pintype "bidirectional"))
      (node (ref "J22") (pin "GNDBREAK") (pinfunction "GNDBREAK_GNDBREAK") (pintype "bidirectional"))
      (node (ref "R45") (pin "4") (pinfunction "4_4") (pintype "passive"))
      (node (ref "U10") (pin "5") (pinfunction "IO4_5") (pintype "bidirectional"))
    )
    (net (code "116") (name "SRB1_OUT_1") (class "Default")
      (node (ref "J24") (pin "GND") (pinfunction "GND_GND") (pintype "bidirectional"))
      (node (ref "J24") (pin "GNDBREAK") (pinfunction "GNDBREAK_GNDBREAK") (pintype "bidirectional"))
      (node (ref "R14") (pin "4") (pinfunction "4_4") (pintype "passive"))
      (node (ref "U16") (pin "5") (pinfunction "IO4_5") (pintype "bidirectional"))
    )
    (net (code "117") (name "SRB2") (class "Default")
      (node (ref "CA5") (pin "6") (pinfunction "6_6") (pintype "passive"))
      (node (ref "R45") (pin "6") (pinfunction "6_6") (pintype "passive"))
      (node (ref "U1") (pin "18") (pinfunction "SRB2_18") (pintype "bidirectional"))
    )
    (net (code "118") (name "SRB2_1") (class "Default")
      (node (ref "CA10") (pin "6") (pinfunction "6_6") (pintype "passive"))
      (node (ref "R14") (pin "6") (pinfunction "6_6") (pintype "passive"))
      (node (ref "U2") (pin "18") (pinfunction "SRB2_18") (pintype "bidirectional"))
    )
    (net (code "119") (name "SRB2_OUT") (class "Default")
      (node (ref "J22") (pin "PWR") (pinfunction "PWR_PWR") (pintype "bidirectional"))
      (node (ref "R45") (pin "3") (pinfunction "3_3") (pintype "passive"))
      (node (ref "U10") (pin "2") (pinfunction "IO2_2") (pintype "bidirectional"))
    )
    (net (code "120") (name "SRB2_OUT_1") (class "Default")
      (node (ref "J24") (pin "PWR") (pinfunction "PWR_PWR") (pintype "bidirectional"))
      (node (ref "R14") (pin "3") (pinfunction "3_3") (pintype "passive"))
      (node (ref "U16") (pin "2") (pinfunction "IO2_2") (pintype "bidirectional"))
    )
    (net (code "121") (name "START_ADS") (class "Default")
      (node (ref "A1") (pin "P$10") (pinfunction "P10_P$10") (pintype "passive"))
      (node (ref "U1") (pin "38") (pinfunction "START_38") (pintype "input"))
      (node (ref "U2") (pin "38") (pinfunction "START_38") (pintype "input"))
    )
    (net (code "122") (name "unconnected-(A1-P15-PadP$15)") (class "Default")
      (node (ref "A1") (pin "P$15") (pinfunction "P15_P$15") (pintype "passive"))
    )
    (net (code "123") (name "unconnected-(A1-P16-PadP$16)") (class "Default")
      (node (ref "A1") (pin "P$16") (pinfunction "P16_P$16") (pintype "passive"))
    )
    (net (code "124") (name "unconnected-(A1-P17-PadP$17)") (class "Default")
      (node (ref "A1") (pin "P$17") (pinfunction "P17_P$17") (pintype "passive"))
    )
    (net (code "125") (name "unconnected-(A1-P18-PadP$18)") (class "Default")
      (node (ref "A1") (pin "P$18") (pinfunction "P18_P$18") (pintype "passive"))
    )
    (net (code "126") (name "unconnected-(A1-P21-PadP$21)") (class "Default")
      (node (ref "A1") (pin "P$21") (pinfunction "P21_P$21") (pintype "passive"))
    )
    (net (code "127") (name "unconnected-(A1-P22-PadP$22)") (class "Default")
      (node (ref "A1") (pin "P$22") (pinfunction "P22_P$22") (pintype "passive"))
    )
    (net (code "128") (name "unconnected-(A1-P23-PadP$23)") (class "Default")
      (node (ref "A1") (pin "P$23") (pinfunction "P23_P$23") (pintype "passive"))
    )
    (net (code "129") (name "unconnected-(A1-P24-PadP$24)") (class "Default")
      (node (ref "A1") (pin "P$24") (pinfunction "P24_P$24") (pintype "passive"))
    )
    (net (code "130") (name "unconnected-(A1-P25-PadP$25)") (class "Default")
      (node (ref "A1") (pin "P$25") (pinfunction "P25_P$25") (pintype "passive"))
    )
    (net (code "131") (name "unconnected-(A1-P26-PadP$26)") (class "Default")
      (node (ref "A1") (pin "P$26") (pinfunction "P26_P$26") (pintype "passive"))
    )
    (net (code "132") (name "unconnected-(A1-P29-PadP$29)") (class "Default")
      (node (ref "A1") (pin "P$29") (pinfunction "P29_P$29") (pintype "passive"))
    )
    (net (code "133") (name "unconnected-(A1-P30-PadP$30)") (class "Default")
      (node (ref "A1") (pin "P$30") (pinfunction "P30_P$30") (pintype "passive"))
    )
    (net (code "134") (name "unconnected-(A1-PadD+)") (class "Default")
      (node (ref "A1") (pin "D+") (pinfunction "D+_D+") (pintype "passive"))
    )
    (net (code "135") (name "unconnected-(A1-PadD-)") (class "Default")
      (node (ref "A1") (pin "D-") (pinfunction "D-_D-") (pintype "passive"))
    )
    (net (code "136") (name "unconnected-(A1-PadIF+)") (class "Default")
      (node (ref "A1") (pin "IF+") (pinfunction "IF+_IF+") (pintype "passive"))
    )
    (net (code "137") (name "unconnected-(A1-PadIF-)") (class "Default")
      (node (ref "A1") (pin "IF-") (pinfunction "IF-_IF-") (pintype "passive"))
    )
    (net (code "138") (name "unconnected-(A1-PadNR)") (class "Default")
      (node (ref "A1") (pin "NR") (pinfunction "NR_NR") (pintype "passive"))
    )
    (net (code "139") (name "unconnected-(A1-PadRD+)") (class "Default")
      (node (ref "A1") (pin "RD+") (pinfunction "RD+_RD+") (pintype "passive"))
    )
    (net (code "140") (name "unconnected-(A1-PadRD-)") (class "Default")
      (node (ref "A1") (pin "RD-") (pinfunction "RD-_RD-") (pintype "passive"))
    )
    (net (code "141") (name "unconnected-(A1-PadTD+)") (class "Default")
      (node (ref "A1") (pin "TD+") (pinfunction "TD+_TD+") (pintype "passive"))
    )
    (net (code "142") (name "unconnected-(A1-PadTD-)") (class "Default")
      (node (ref "A1") (pin "TD-") (pinfunction "TD-_TD-") (pintype "passive"))
    )
    (net (code "143") (name "unconnected-(A1-PadVB)") (class "Default")
      (node (ref "A1") (pin "VB") (pinfunction "VB_VB") (pintype "passive"))
    )
    (net (code "144") (name "unconnected-(A1-PadVU)") (class "Default")
      (node (ref "A1") (pin "VU") (pinfunction "VU_VU") (pintype "passive"))
    )
    (net (code "145") (name "unconnected-(J1-Pad1)") (class "Default")
      (node (ref "J1") (pin "1") (pinfunction "1_1") (pintype "no_connect"))
    )
    (net (code "146") (name "unconnected-(J1-Pad8)") (class "Default")
      (node (ref "J1") (pin "8") (pinfunction "8_8") (pintype "no_connect"))
    )
    (net (code "147") (name "unconnected-(J1-Pad9)") (class "Default")
      (node (ref "J1") (pin "9") (pinfunction "9_9") (pintype "no_connect"))
    )
    (net (code "148") (name "unconnected-(J1-Pad10)") (class "Default")
      (node (ref "J1") (pin "10") (pinfunction "10_10") (pintype "no_connect"))
    )
    (net (code "149") (name "unconnected-(J4-D+-Pad3)") (class "Default")
      (node (ref "J4") (pin "3") (pinfunction "D+_3") (pintype "passive"))
    )
    (net (code "150") (name "unconnected-(J4-D--Pad2)") (class "Default")
      (node (ref "J4") (pin "2") (pinfunction "D-_2") (pintype "passive"))
    )
    (net (code "151") (name "unconnected-(J4-ID-Pad4)") (class "Default")
      (node (ref "J4") (pin "4") (pinfunction "ID_4") (pintype "passive"))
    )
    (net (code "152") (name "unconnected-(SW1-Pad2)") (class "Default")
      (node (ref "SW1") (pin "2") (pinfunction "2_2") (pintype "no_connect"))
    )
    (net (code "153") (name "unconnected-(U1-GPIO1-Pad42)") (class "Default")
      (node (ref "U1") (pin "42") (pinfunction "GPIO1_42") (pintype "no_connect"))
    )
    (net (code "154") (name "unconnected-(U1-GPIO2-Pad44)") (class "Default")
      (node (ref "U1") (pin "44") (pinfunction "GPIO2_44") (pintype "no_connect"))
    )
    (net (code "155") (name "unconnected-(U1-GPIO3-Pad45)") (class "Default")
      (node (ref "U1") (pin "45") (pinfunction "GPIO3_45") (pintype "no_connect"))
    )
    (net (code "156") (name "unconnected-(U1-GPIO4-Pad46)") (class "Default")
      (node (ref "U1") (pin "46") (pinfunction "GPIO4_46") (pintype "no_connect"))
    )
    (net (code "157") (name "unconnected-(U1-NC-Pad29)") (class "Default")
      (node (ref "U1") (pin "29") (pinfunction "NC_29") (pintype "no_connect"))
    )
    (net (code "158") (name "unconnected-(U1-NC_2-Pad27)") (class "Default")
      (node (ref "U1") (pin "27") (pinfunction "NC_2_27") (pintype "no_connect"))
    )
    (net (code "159") (name "unconnected-(U2-GPIO1-Pad42)") (class "Default")
      (node (ref "U2") (pin "42") (pinfunction "GPIO1_42") (pintype "no_connect"))
    )
    (net (code "160") (name "unconnected-(U2-GPIO2-Pad44)") (class "Default")
      (node (ref "U2") (pin "44") (pinfunction "GPIO2_44") (pintype "no_connect"))
    )
    (net (code "161") (name "unconnected-(U2-GPIO3-Pad45)") (class "Default")
      (node (ref "U2") (pin "45") (pinfunction "GPIO3_45") (pintype "no_connect"))
    )
    (net (code "162") (name "unconnected-(U2-GPIO4-Pad46)") (class "Default")
      (node (ref "U2") (pin "46") (pinfunction "GPIO4_46") (pintype "no_connect"))
    )
    (net (code "163") (name "unconnected-(U2-NC-Pad29)") (class "Default")
      (node (ref "U2") (pin "29") (pinfunction "NC_29") (pintype "no_connect"))
    )
    (net (code "164") (name "unconnected-(U2-NC_2-Pad27)") (class "Default")
      (node (ref "U2") (pin "27") (pinfunction "NC_2_27") (pintype "no_connect"))
    )
    (net (code "165") (name "unconnected-(U2-~{DRDY}-Pad47)") (class "Default")
      (node (ref "U2") (pin "47") (pinfunction "~{DRDY}_47") (pintype "output"))
    )
    (net (code "166") (name "unconnected-(U3-PGOOD-Pad5)") (class "Default")
      (node (ref "U3") (pin "5") (pinfunction "PGOOD_5") (pintype "no_connect"))
    )
    (net (code "167") (name "unconnected-(U6-IO1-Pad1)") (class "Default")
      (node (ref "U6") (pin "1") (pinfunction "IO1_1") (pintype "bidirectional"))
    )
    (net (code "168") (name "unconnected-(U6-NC-Pad6)") (class "Default")
      (node (ref "U6") (pin "6") (pinfunction "NC_6") (pintype "no_connect"))
    )
    (net (code "169") (name "unconnected-(U7-NC-Pad6)") (class "Default")
      (node (ref "U7") (pin "6") (pinfunction "NC_6") (pintype "no_connect"))
    )
    (net (code "170") (name "unconnected-(U8-NC-Pad6)") (class "Default")
      (node (ref "U8") (pin "6") (pinfunction "NC_6") (pintype "no_connect"))
    )
    (net (code "171") (name "unconnected-(U9-NC-Pad6)") (class "Default")
      (node (ref "U9") (pin "6") (pinfunction "NC_6") (pintype "no_connect"))
    )
    (net (code "172") (name "unconnected-(U10-IO3-Pad4)") (class "Default")
      (node (ref "U10") (pin "4") (pinfunction "IO3_4") (pintype "bidirectional"))
    )
    (net (code "173") (name "unconnected-(U10-NC-Pad6)") (class "Default")
      (node (ref "U10") (pin "6") (pinfunction "NC_6") (pintype "no_connect"))
    )
    (net (code "174") (name "unconnected-(U11-IO4-Pad5)") (class "Default")
      (node (ref "U11") (pin "5") (pinfunction "IO4_5") (pintype "bidirectional"))
    )
    (net (code "175") (name "unconnected-(U11-NC-Pad6)") (class "Default")
      (node (ref "U11") (pin "6") (pinfunction "NC_6") (pintype "no_connect"))
    )
    (net (code "176") (name "unconnected-(U12-IO1-Pad1)") (class "Default")
      (node (ref "U12") (pin "1") (pinfunction "IO1_1") (pintype "bidirectional"))
    )
    (net (code "177") (name "unconnected-(U12-NC-Pad6)") (class "Default")
      (node (ref "U12") (pin "6") (pinfunction "NC_6") (pintype "no_connect"))
    )
    (net (code "178") (name "unconnected-(U13-NC-Pad6)") (class "Default")
      (node (ref "U13") (pin "6") (pinfunction "NC_6") (pintype "no_connect"))
    )
    (net (code "179") (name "unconnected-(U14-NC-Pad6)") (class "Default")
      (node (ref "U14") (pin "6") (pinfunction "NC_6") (pintype "no_connect"))
    )
    (net (code "180") (name "unconnected-(U15-NC-Pad6)") (class "Default")
      (node (ref "U15") (pin "6") (pinfunction "NC_6") (pintype "no_connect"))
    )
    (net (code "181") (name "unconnected-(U16-IO3-Pad4)") (class "Default")
      (node (ref "U16") (pin "4") (pinfunction "IO3_4") (pintype "bidirectional"))
    )
    (net (code "182") (name "unconnected-(U16-NC-Pad6)") (class "Default")
      (node (ref "U16") (pin "6") (pinfunction "NC_6") (pintype "no_connect"))
    )
    (net (code "183") (name "unconnected-(U17-IO4-Pad5)") (class "Default")
      (node (ref "U17") (pin "5") (pinfunction "IO4_5") (pintype "bidirectional"))
    )
    (net (code "184") (name "unconnected-(U17-NC-Pad6)") (class "Default")
      (node (ref "U17") (pin "6") (pinfunction "NC_6") (pintype "no_connect"))
    )
    (net (code "185") (name "~{CS}_ADS") (class "Default")
      (node (ref "A1") (pin "P$9") (pinfunction "P9_P$9") (pintype "passive"))
      (node (ref "U1") (pin "39") (pinfunction "~{CS}_39") (pintype "input"))
    )
    (net (code "186") (name "~{CS}_ADS_1") (class "Default")
      (node (ref "A1") (pin "P$20") (pinfunction "P20_P$20") (pintype "passive"))
      (node (ref "U2") (pin "39") (pinfunction "~{CS}_39") (pintype "input"))
    )
    (net (code "187") (name "~{CS}_SD") (class "Default")
      (node (ref "A1") (pin "P$14") (pinfunction "P14_P$14") (pintype "passive"))
      (node (ref "J1") (pin "2") (pinfunction "2_2") (pintype "passive"))
    )
    (net (code "188") (name "~{INT}") (class "Default")
      (node (ref "A1") (pin "P$8") (pinfunction "P8_P$8") (pintype "passive"))
      (node (ref "U1") (pin "47") (pinfunction "~{DRDY}_47") (pintype "output"))
    )
    (net (code "189") (name "~{RESET}_ADS") (class "Default")
      (node (ref "A1") (pin "P$19") (pinfunction "P19_P$19") (pintype "passive"))
      (node (ref "U1") (pin "36") (pinfunction "~{RESET}_36") (pintype "input"))
      (node (ref "U2") (pin "36") (pinfunction "~{RESET}_36") (pintype "input"))
    )
  )
)
